# DE-020224_02.net
KiCad netlist of a schematic drawn in Altium Designer
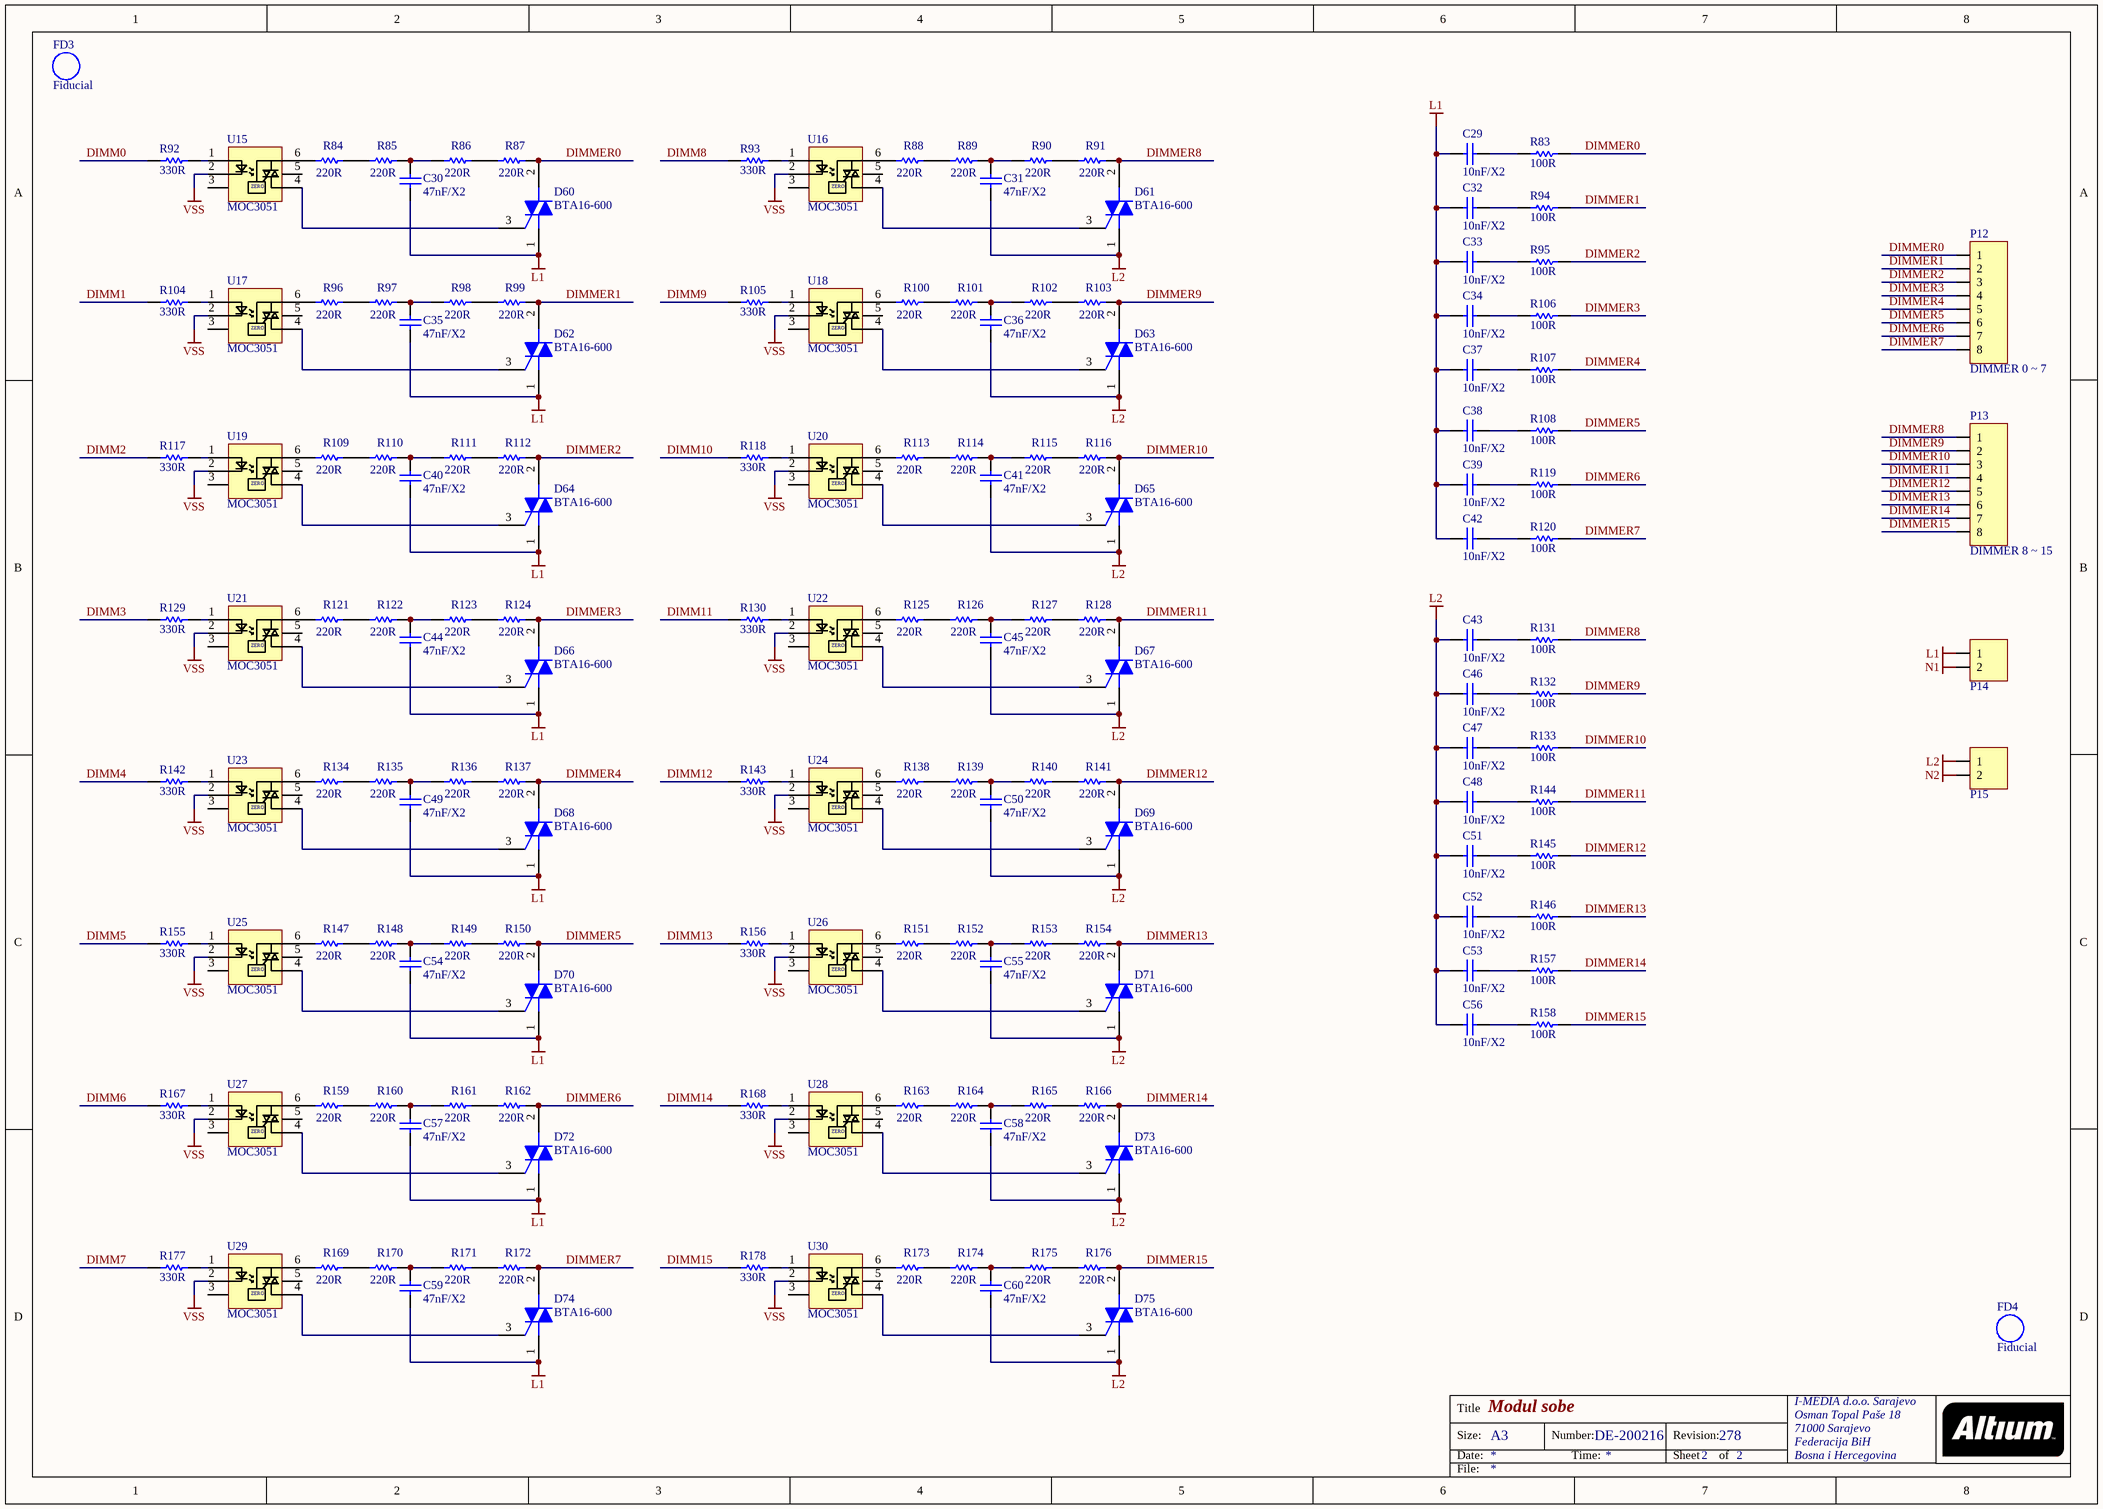
[diagram p0: DE-020224_02.SchDoc]

(export (version "E")
  (design (tool "Eeschema 10.0.6"))
  (components
    (comp (ref "C29")
      (value "10nF/X2")
      (footprint "VP52-2.5")
      (description "Dipped Radial Multilayer Ceramic Capacitor COG (NPO): 10nF")
      (fields (field (name "PUBLISHER") "Altium Limited"))
      (libsource (lib "Vishay Vitramon Ceramic Dipped Capacitor") (part "VP52BA103"))
    )
    (comp (ref "C30")
      (value "47nF/X2")
      (footprint "VP52-2.5")
      (description "Dipped Radial Multilayer Ceramic Capacitor COG (NPO): 10nF")
      (fields (field (name "PUBLISHER") "Altium Limited"))
      (libsource (lib "Vishay Vitramon Ceramic Dipped Capacitor") (part "VP52BA103"))
    )
    (comp (ref "C31")
      (value "47nF/X2")
      (footprint "VP52-2.5")
      (description "Dipped Radial Multilayer Ceramic Capacitor COG (NPO): 10nF")
      (fields (field (name "PUBLISHER") "Altium Limited"))
      (libsource (lib "Vishay Vitramon Ceramic Dipped Capacitor") (part "VP52BA103"))
    )
    (comp (ref "C32")
      (value "10nF/X2")
      (footprint "VP52-2.5")
      (description "Dipped Radial Multilayer Ceramic Capacitor COG (NPO): 10nF")
      (fields (field (name "PUBLISHER") "Altium Limited"))
      (libsource (lib "Vishay Vitramon Ceramic Dipped Capacitor") (part "VP52BA103"))
    )
    (comp (ref "C33")
      (value "10nF/X2")
      (footprint "VP52-2.5")
      (description "Dipped Radial Multilayer Ceramic Capacitor COG (NPO): 10nF")
      (fields (field (name "PUBLISHER") "Altium Limited"))
      (libsource (lib "Vishay Vitramon Ceramic Dipped Capacitor") (part "VP52BA103"))
    )
    (comp (ref "C34")
      (value "10nF/X2")
      (footprint "VP52-2.5")
      (description "Dipped Radial Multilayer Ceramic Capacitor COG (NPO): 10nF")
      (fields (field (name "PUBLISHER") "Altium Limited"))
      (libsource (lib "Vishay Vitramon Ceramic Dipped Capacitor") (part "VP52BA103"))
    )
    (comp (ref "C35")
      (value "47nF/X2")
      (footprint "VP52-2.5")
      (description "Dipped Radial Multilayer Ceramic Capacitor COG (NPO): 10nF")
      (fields (field (name "PUBLISHER") "Altium Limited"))
      (libsource (lib "Vishay Vitramon Ceramic Dipped Capacitor") (part "VP52BA103"))
    )
    (comp (ref "C36")
      (value "47nF/X2")
      (footprint "VP52-2.5")
      (description "Dipped Radial Multilayer Ceramic Capacitor COG (NPO): 10nF")
      (fields (field (name "PUBLISHER") "Altium Limited"))
      (libsource (lib "Vishay Vitramon Ceramic Dipped Capacitor") (part "VP52BA103"))
    )
    (comp (ref "C37")
      (value "10nF/X2")
      (footprint "VP52-2.5")
      (description "Dipped Radial Multilayer Ceramic Capacitor COG (NPO): 10nF")
      (fields (field (name "PUBLISHER") "Altium Limited"))
      (libsource (lib "Vishay Vitramon Ceramic Dipped Capacitor") (part "VP52BA103"))
    )
    (comp (ref "C38")
      (value "10nF/X2")
      (footprint "VP52-2.5")
      (description "Dipped Radial Multilayer Ceramic Capacitor COG (NPO): 10nF")
      (fields (field (name "PUBLISHER") "Altium Limited"))
      (libsource (lib "Vishay Vitramon Ceramic Dipped Capacitor") (part "VP52BA103"))
    )
    (comp (ref "C39")
      (value "10nF/X2")
      (footprint "VP52-2.5")
      (description "Dipped Radial Multilayer Ceramic Capacitor COG (NPO): 10nF")
      (fields (field (name "PUBLISHER") "Altium Limited"))
      (libsource (lib "Vishay Vitramon Ceramic Dipped Capacitor") (part "VP52BA103"))
    )
    (comp (ref "C40")
      (value "47nF/X2")
      (footprint "VP52-2.5")
      (description "Dipped Radial Multilayer Ceramic Capacitor COG (NPO): 10nF")
      (fields (field (name "PUBLISHER") "Altium Limited"))
      (libsource (lib "Vishay Vitramon Ceramic Dipped Capacitor") (part "VP52BA103"))
    )
    (comp (ref "C41")
      (value "47nF/X2")
      (footprint "VP52-2.5")
      (description "Dipped Radial Multilayer Ceramic Capacitor COG (NPO): 10nF")
      (fields (field (name "PUBLISHER") "Altium Limited"))
      (libsource (lib "Vishay Vitramon Ceramic Dipped Capacitor") (part "VP52BA103"))
    )
    (comp (ref "C42")
      (value "10nF/X2")
      (footprint "VP52-2.5")
      (description "Dipped Radial Multilayer Ceramic Capacitor COG (NPO): 10nF")
      (fields (field (name "PUBLISHER") "Altium Limited"))
      (libsource (lib "Vishay Vitramon Ceramic Dipped Capacitor") (part "VP52BA103"))
    )
    (comp (ref "C43")
      (value "10nF/X2")
      (footprint "VP52-2.5")
      (description "Dipped Radial Multilayer Ceramic Capacitor COG (NPO): 10nF")
      (fields (field (name "PUBLISHER") "Altium Limited"))
      (libsource (lib "Vishay Vitramon Ceramic Dipped Capacitor") (part "VP52BA103"))
    )
    (comp (ref "C44")
      (value "47nF/X2")
      (footprint "VP52-2.5")
      (description "Dipped Radial Multilayer Ceramic Capacitor COG (NPO): 10nF")
      (fields (field (name "PUBLISHER") "Altium Limited"))
      (libsource (lib "Vishay Vitramon Ceramic Dipped Capacitor") (part "VP52BA103"))
    )
    (comp (ref "C45")
      (value "47nF/X2")
      (footprint "VP52-2.5")
      (description "Dipped Radial Multilayer Ceramic Capacitor COG (NPO): 10nF")
      (fields (field (name "PUBLISHER") "Altium Limited"))
      (libsource (lib "Vishay Vitramon Ceramic Dipped Capacitor") (part "VP52BA103"))
    )
    (comp (ref "C46")
      (value "10nF/X2")
      (footprint "VP52-2.5")
      (description "Dipped Radial Multilayer Ceramic Capacitor COG (NPO): 10nF")
      (fields (field (name "PUBLISHER") "Altium Limited"))
      (libsource (lib "Vishay Vitramon Ceramic Dipped Capacitor") (part "VP52BA103"))
    )
    (comp (ref "C47")
      (value "10nF/X2")
      (footprint "VP52-2.5")
      (description "Dipped Radial Multilayer Ceramic Capacitor COG (NPO): 10nF")
      (fields (field (name "PUBLISHER") "Altium Limited"))
      (libsource (lib "Vishay Vitramon Ceramic Dipped Capacitor") (part "VP52BA103"))
    )
    (comp (ref "C48")
      (value "10nF/X2")
      (footprint "VP52-2.5")
      (description "Dipped Radial Multilayer Ceramic Capacitor COG (NPO): 10nF")
      (fields (field (name "PUBLISHER") "Altium Limited"))
      (libsource (lib "Vishay Vitramon Ceramic Dipped Capacitor") (part "VP52BA103"))
    )
    (comp (ref "C49")
      (value "47nF/X2")
      (footprint "VP52-2.5")
      (description "Dipped Radial Multilayer Ceramic Capacitor COG (NPO): 10nF")
      (fields (field (name "PUBLISHER") "Altium Limited"))
      (libsource (lib "Vishay Vitramon Ceramic Dipped Capacitor") (part "VP52BA103"))
    )
    (comp (ref "C50")
      (value "47nF/X2")
      (footprint "VP52-2.5")
      (description "Dipped Radial Multilayer Ceramic Capacitor COG (NPO): 10nF")
      (fields (field (name "PUBLISHER") "Altium Limited"))
      (libsource (lib "Vishay Vitramon Ceramic Dipped Capacitor") (part "VP52BA103"))
    )
    (comp (ref "C51")
      (value "10nF/X2")
      (footprint "VP52-2.5")
      (description "Dipped Radial Multilayer Ceramic Capacitor COG (NPO): 10nF")
      (fields (field (name "PUBLISHER") "Altium Limited"))
      (libsource (lib "Vishay Vitramon Ceramic Dipped Capacitor") (part "VP52BA103"))
    )
    (comp (ref "C52")
      (value "10nF/X2")
      (footprint "VP52-2.5")
      (description "Dipped Radial Multilayer Ceramic Capacitor COG (NPO): 10nF")
      (fields (field (name "PUBLISHER") "Altium Limited"))
      (libsource (lib "Vishay Vitramon Ceramic Dipped Capacitor") (part "VP52BA103"))
    )
    (comp (ref "C53")
      (value "10nF/X2")
      (footprint "VP52-2.5")
      (description "Dipped Radial Multilayer Ceramic Capacitor COG (NPO): 10nF")
      (fields (field (name "PUBLISHER") "Altium Limited"))
      (libsource (lib "Vishay Vitramon Ceramic Dipped Capacitor") (part "VP52BA103"))
    )
    (comp (ref "C54")
      (value "47nF/X2")
      (footprint "VP52-2.5")
      (description "Dipped Radial Multilayer Ceramic Capacitor COG (NPO): 10nF")
      (fields (field (name "PUBLISHER") "Altium Limited"))
      (libsource (lib "Vishay Vitramon Ceramic Dipped Capacitor") (part "VP52BA103"))
    )
    (comp (ref "C55")
      (value "47nF/X2")
      (footprint "VP52-2.5")
      (description "Dipped Radial Multilayer Ceramic Capacitor COG (NPO): 10nF")
      (fields (field (name "PUBLISHER") "Altium Limited"))
      (libsource (lib "Vishay Vitramon Ceramic Dipped Capacitor") (part "VP52BA103"))
    )
    (comp (ref "C56")
      (value "10nF/X2")
      (footprint "VP52-2.5")
      (description "Dipped Radial Multilayer Ceramic Capacitor COG (NPO): 10nF")
      (fields (field (name "PUBLISHER") "Altium Limited"))
      (libsource (lib "Vishay Vitramon Ceramic Dipped Capacitor") (part "VP52BA103"))
    )
    (comp (ref "C57")
      (value "47nF/X2")
      (footprint "VP52-2.5")
      (description "Dipped Radial Multilayer Ceramic Capacitor COG (NPO): 10nF")
      (fields (field (name "PUBLISHER") "Altium Limited"))
      (libsource (lib "Vishay Vitramon Ceramic Dipped Capacitor") (part "VP52BA103"))
    )
    (comp (ref "C58")
      (value "47nF/X2")
      (footprint "VP52-2.5")
      (description "Dipped Radial Multilayer Ceramic Capacitor COG (NPO): 10nF")
      (fields (field (name "PUBLISHER") "Altium Limited"))
      (libsource (lib "Vishay Vitramon Ceramic Dipped Capacitor") (part "VP52BA103"))
    )
    (comp (ref "C59")
      (value "47nF/X2")
      (footprint "VP52-2.5")
      (description "Dipped Radial Multilayer Ceramic Capacitor COG (NPO): 10nF")
      (fields (field (name "PUBLISHER") "Altium Limited"))
      (libsource (lib "Vishay Vitramon Ceramic Dipped Capacitor") (part "VP52BA103"))
    )
    (comp (ref "C60")
      (value "47nF/X2")
      (footprint "VP52-2.5")
      (description "Dipped Radial Multilayer Ceramic Capacitor COG (NPO): 10nF")
      (fields (field (name "PUBLISHER") "Altium Limited"))
      (libsource (lib "Vishay Vitramon Ceramic Dipped Capacitor") (part "VP52BA103"))
    )
    (comp (ref "D60")
      (value "BTA16-600")
      (footprint "ONSC-TO-220-3-221A-07")
      (description "Triacs, Silicon Bidirectional Thyristor, 3-Pin TO-220, Pb-Free, Tube")
      (fields (field (name "MANUFACTURER") "On Semiconductor") (field (name "PARTNUMBER") "BTA08-600BW3G"))
      (libsource (lib "DE-020224") (part "BTA08-600BW3G"))
    )
    (comp (ref "D61")
      (value "BTA16-600")
      (footprint "ONSC-TO-220-3-221A-07")
      (description "Triacs, Silicon Bidirectional Thyristor, 3-Pin TO-220, Pb-Free, Tube")
      (fields (field (name "MANUFACTURER") "On Semiconductor") (field (name "PARTNUMBER") "BTA08-600BW3G"))
      (libsource (lib "DE-020224") (part "BTA08-600BW3G"))
    )
    (comp (ref "D62")
      (value "BTA16-600")
      (footprint "ONSC-TO-220-3-221A-07")
      (description "Triacs, Silicon Bidirectional Thyristor, 3-Pin TO-220, Pb-Free, Tube")
      (fields (field (name "MANUFACTURER") "On Semiconductor") (field (name "PARTNUMBER") "BTA08-600BW3G"))
      (libsource (lib "DE-020224") (part "BTA08-600BW3G"))
    )
    (comp (ref "D63")
      (value "BTA16-600")
      (footprint "ONSC-TO-220-3-221A-07")
      (description "Triacs, Silicon Bidirectional Thyristor, 3-Pin TO-220, Pb-Free, Tube")
      (fields (field (name "MANUFACTURER") "On Semiconductor") (field (name "PARTNUMBER") "BTA08-600BW3G"))
      (libsource (lib "DE-020224") (part "BTA08-600BW3G"))
    )
    (comp (ref "D64")
      (value "BTA16-600")
      (footprint "ONSC-TO-220-3-221A-07")
      (description "Triacs, Silicon Bidirectional Thyristor, 3-Pin TO-220, Pb-Free, Tube")
      (fields (field (name "MANUFACTURER") "On Semiconductor") (field (name "PARTNUMBER") "BTA08-600BW3G"))
      (libsource (lib "DE-020224") (part "BTA08-600BW3G"))
    )
    (comp (ref "D65")
      (value "BTA16-600")
      (footprint "ONSC-TO-220-3-221A-07")
      (description "Triacs, Silicon Bidirectional Thyristor, 3-Pin TO-220, Pb-Free, Tube")
      (fields (field (name "MANUFACTURER") "On Semiconductor") (field (name "PARTNUMBER") "BTA08-600BW3G"))
      (libsource (lib "DE-020224") (part "BTA08-600BW3G"))
    )
    (comp (ref "D66")
      (value "BTA16-600")
      (footprint "ONSC-TO-220-3-221A-07")
      (description "Triacs, Silicon Bidirectional Thyristor, 3-Pin TO-220, Pb-Free, Tube")
      (fields (field (name "MANUFACTURER") "On Semiconductor") (field (name "PARTNUMBER") "BTA08-600BW3G"))
      (libsource (lib "DE-020224") (part "BTA08-600BW3G"))
    )
    (comp (ref "D67")
      (value "BTA16-600")
      (footprint "ONSC-TO-220-3-221A-07")
      (description "Triacs, Silicon Bidirectional Thyristor, 3-Pin TO-220, Pb-Free, Tube")
      (fields (field (name "MANUFACTURER") "On Semiconductor") (field (name "PARTNUMBER") "BTA08-600BW3G"))
      (libsource (lib "DE-020224") (part "BTA08-600BW3G"))
    )
    (comp (ref "D68")
      (value "BTA16-600")
      (footprint "ONSC-TO-220-3-221A-07")
      (description "Triacs, Silicon Bidirectional Thyristor, 3-Pin TO-220, Pb-Free, Tube")
      (fields (field (name "MANUFACTURER") "On Semiconductor") (field (name "PARTNUMBER") "BTA08-600BW3G"))
      (libsource (lib "DE-020224") (part "BTA08-600BW3G"))
    )
    (comp (ref "D69")
      (value "BTA16-600")
      (footprint "ONSC-TO-220-3-221A-07")
      (description "Triacs, Silicon Bidirectional Thyristor, 3-Pin TO-220, Pb-Free, Tube")
      (fields (field (name "MANUFACTURER") "On Semiconductor") (field (name "PARTNUMBER") "BTA08-600BW3G"))
      (libsource (lib "DE-020224") (part "BTA08-600BW3G"))
    )
    (comp (ref "D70")
      (value "BTA16-600")
      (footprint "ONSC-TO-220-3-221A-07")
      (description "Triacs, Silicon Bidirectional Thyristor, 3-Pin TO-220, Pb-Free, Tube")
      (fields (field (name "MANUFACTURER") "On Semiconductor") (field (name "PARTNUMBER") "BTA08-600BW3G"))
      (libsource (lib "DE-020224") (part "BTA08-600BW3G"))
    )
    (comp (ref "D71")
      (value "BTA16-600")
      (footprint "ONSC-TO-220-3-221A-07")
      (description "Triacs, Silicon Bidirectional Thyristor, 3-Pin TO-220, Pb-Free, Tube")
      (fields (field (name "MANUFACTURER") "On Semiconductor") (field (name "PARTNUMBER") "BTA08-600BW3G"))
      (libsource (lib "DE-020224") (part "BTA08-600BW3G"))
    )
    (comp (ref "D72")
      (value "BTA16-600")
      (footprint "ONSC-TO-220-3-221A-07")
      (description "Triacs, Silicon Bidirectional Thyristor, 3-Pin TO-220, Pb-Free, Tube")
      (fields (field (name "MANUFACTURER") "On Semiconductor") (field (name "PARTNUMBER") "BTA08-600BW3G"))
      (libsource (lib "DE-020224") (part "BTA08-600BW3G"))
    )
    (comp (ref "D73")
      (value "BTA16-600")
      (footprint "ONSC-TO-220-3-221A-07")
      (description "Triacs, Silicon Bidirectional Thyristor, 3-Pin TO-220, Pb-Free, Tube")
      (fields (field (name "MANUFACTURER") "On Semiconductor") (field (name "PARTNUMBER") "BTA08-600BW3G"))
      (libsource (lib "DE-020224") (part "BTA08-600BW3G"))
    )
    (comp (ref "D74")
      (value "BTA16-600")
      (footprint "ONSC-TO-220-3-221A-07")
      (description "Triacs, Silicon Bidirectional Thyristor, 3-Pin TO-220, Pb-Free, Tube")
      (fields (field (name "MANUFACTURER") "On Semiconductor") (field (name "PARTNUMBER") "BTA08-600BW3G"))
      (libsource (lib "DE-020224") (part "BTA08-600BW3G"))
    )
    (comp (ref "D75")
      (value "BTA16-600")
      (footprint "ONSC-TO-220-3-221A-07")
      (description "Triacs, Silicon Bidirectional Thyristor, 3-Pin TO-220, Pb-Free, Tube")
      (fields (field (name "MANUFACTURER") "On Semiconductor") (field (name "PARTNUMBER") "BTA08-600BW3G"))
      (libsource (lib "DE-020224") (part "BTA08-600BW3G"))
    )
    (comp (ref "FD3")
      (value "Fiducial")
      (footprint "Fiducial")
      (description "Fiduchial mark")
      (libsource (lib "DE-200216_02_1") (part "Fiduchial"))
    )
    (comp (ref "FD4")
      (value "Fiducial")
      (footprint "Fiducial")
      (description "Fiduchial mark")
      (libsource (lib "DE-200216_02_1") (part "Fiduchial"))
    )
    (comp (ref "P12")
      (value "DIMMER 0 ~ 7")
      (footprint "TERMINAL BLOK 8")
      (description "8 pin terminal cable connector")
      (libsource (lib "DE-020224") (part "TERMINAL BLOK 8 MANJI"))
    )
    (comp (ref "P13")
      (value "DIMMER 8 ~ 15")
      (footprint "TERMINAL BLOK 8")
      (description "8 pin terminal cable connector")
      (libsource (lib "DE-020224") (part "TERMINAL BLOK 8 MANJI"))
    )
    (comp (ref "P14")
      (value "TERMINAL BLOK 2")
      (footprint "TERMINAL BLOK 2")
      (description "2 pinski terminal blok")
      (libsource (lib "DE-020224") (part "TERMINAL BLOK 2"))
    )
    (comp (ref "P15")
      (value "TERMINAL BLOK 2")
      (footprint "TERMINAL BLOK 2")
      (description "2 pinski terminal blok")
      (libsource (lib "DE-020224") (part "TERMINAL BLOK 2"))
    )
    (comp (ref "R83")
      (value "100R")
      (footprint "R6.35x2.3")
      (description "Metal Oxide Film Resistor, 0.1 Ohm to 47k Ohm Range, 2% and 5% Tolerance, 0.5 W")
      (fields (field (name "PUBLISHER") "Altium Limited"))
      (libsource (lib "DE-020224") (part "ERG12"))
    )
    (comp (ref "R84")
      (value "220R")
      (footprint "ERA-0805")
      (fields (field (name "PUBLISHER") "Altium Limited"))
      (libsource (lib "DE-020224") (part "ERA6Y"))
    )
    (comp (ref "R85")
      (value "220R")
      (footprint "ERA-0805")
      (fields (field (name "PUBLISHER") "Altium Limited"))
      (libsource (lib "DE-020224") (part "ERA6Y"))
    )
    (comp (ref "R86")
      (value "220R")
      (footprint "ERA-0805")
      (fields (field (name "PUBLISHER") "Altium Limited"))
      (libsource (lib "DE-020224") (part "ERA6Y"))
    )
    (comp (ref "R87")
      (value "220R")
      (footprint "ERA-0805")
      (fields (field (name "PUBLISHER") "Altium Limited"))
      (libsource (lib "DE-020224") (part "ERA6Y"))
    )
    (comp (ref "R88")
      (value "220R")
      (footprint "ERA-0805")
      (fields (field (name "PUBLISHER") "Altium Limited"))
      (libsource (lib "DE-020224") (part "ERA6Y"))
    )
    (comp (ref "R89")
      (value "220R")
      (footprint "ERA-0805")
      (fields (field (name "PUBLISHER") "Altium Limited"))
      (libsource (lib "DE-020224") (part "ERA6Y"))
    )
    (comp (ref "R90")
      (value "220R")
      (footprint "ERA-0805")
      (fields (field (name "PUBLISHER") "Altium Limited"))
      (libsource (lib "DE-020224") (part "ERA6Y"))
    )
    (comp (ref "R91")
      (value "220R")
      (footprint "ERA-0805")
      (fields (field (name "PUBLISHER") "Altium Limited"))
      (libsource (lib "DE-020224") (part "ERA6Y"))
    )
    (comp (ref "R92")
      (value "330R")
      (footprint "ERA-0603")
      (fields (field (name "PUBLISHER") "Altium Limited"))
      (libsource (lib "DE-020224") (part "ERA3Y"))
    )
    (comp (ref "R93")
      (value "330R")
      (footprint "ERA-0603")
      (fields (field (name "PUBLISHER") "Altium Limited"))
      (libsource (lib "DE-020224") (part "ERA3Y"))
    )
    (comp (ref "R94")
      (value "100R")
      (footprint "R6.35x2.3")
      (description "Metal Oxide Film Resistor, 0.1 Ohm to 47k Ohm Range, 2% and 5% Tolerance, 0.5 W")
      (fields (field (name "PUBLISHER") "Altium Limited"))
      (libsource (lib "DE-020224") (part "ERG12"))
    )
    (comp (ref "R95")
      (value "100R")
      (footprint "R6.35x2.3")
      (description "Metal Oxide Film Resistor, 0.1 Ohm to 47k Ohm Range, 2% and 5% Tolerance, 0.5 W")
      (fields (field (name "PUBLISHER") "Altium Limited"))
      (libsource (lib "DE-020224") (part "ERG12"))
    )
    (comp (ref "R96")
      (value "220R")
      (footprint "ERA-0805")
      (fields (field (name "PUBLISHER") "Altium Limited"))
      (libsource (lib "DE-020224") (part "ERA6Y"))
    )
    (comp (ref "R97")
      (value "220R")
      (footprint "ERA-0805")
      (fields (field (name "PUBLISHER") "Altium Limited"))
      (libsource (lib "DE-020224") (part "ERA6Y"))
    )
    (comp (ref "R98")
      (value "220R")
      (footprint "ERA-0805")
      (fields (field (name "PUBLISHER") "Altium Limited"))
      (libsource (lib "DE-020224") (part "ERA6Y"))
    )
    (comp (ref "R99")
      (value "220R")
      (footprint "ERA-0805")
      (fields (field (name "PUBLISHER") "Altium Limited"))
      (libsource (lib "DE-020224") (part "ERA6Y"))
    )
    (comp (ref "R100")
      (value "220R")
      (footprint "ERA-0805")
      (fields (field (name "PUBLISHER") "Altium Limited"))
      (libsource (lib "DE-020224") (part "ERA6Y"))
    )
    (comp (ref "R101")
      (value "220R")
      (footprint "ERA-0805")
      (fields (field (name "PUBLISHER") "Altium Limited"))
      (libsource (lib "DE-020224") (part "ERA6Y"))
    )
    (comp (ref "R102")
      (value "220R")
      (footprint "ERA-0805")
      (fields (field (name "PUBLISHER") "Altium Limited"))
      (libsource (lib "DE-020224") (part "ERA6Y"))
    )
    (comp (ref "R103")
      (value "220R")
      (footprint "ERA-0805")
      (fields (field (name "PUBLISHER") "Altium Limited"))
      (libsource (lib "DE-020224") (part "ERA6Y"))
    )
    (comp (ref "R104")
      (value "330R")
      (footprint "ERA-0603")
      (fields (field (name "PUBLISHER") "Altium Limited"))
      (libsource (lib "DE-020224") (part "ERA3Y"))
    )
    (comp (ref "R105")
      (value "330R")
      (footprint "ERA-0603")
      (fields (field (name "PUBLISHER") "Altium Limited"))
      (libsource (lib "DE-020224") (part "ERA3Y"))
    )
    (comp (ref "R106")
      (value "100R")
      (footprint "R6.35x2.3")
      (description "Metal Oxide Film Resistor, 0.1 Ohm to 47k Ohm Range, 2% and 5% Tolerance, 0.5 W")
      (fields (field (name "PUBLISHER") "Altium Limited"))
      (libsource (lib "DE-020224") (part "ERG12"))
    )
    (comp (ref "R107")
      (value "100R")
      (footprint "R6.35x2.3")
      (description "Metal Oxide Film Resistor, 0.1 Ohm to 47k Ohm Range, 2% and 5% Tolerance, 0.5 W")
      (fields (field (name "PUBLISHER") "Altium Limited"))
      (libsource (lib "DE-020224") (part "ERG12"))
    )
    (comp (ref "R108")
      (value "100R")
      (footprint "R6.35x2.3")
      (description "Metal Oxide Film Resistor, 0.1 Ohm to 47k Ohm Range, 2% and 5% Tolerance, 0.5 W")
      (fields (field (name "PUBLISHER") "Altium Limited"))
      (libsource (lib "DE-020224") (part "ERG12"))
    )
    (comp (ref "R109")
      (value "220R")
      (footprint "ERA-0805")
      (fields (field (name "PUBLISHER") "Altium Limited"))
      (libsource (lib "DE-020224") (part "ERA6Y"))
    )
    (comp (ref "R110")
      (value "220R")
      (footprint "ERA-0805")
      (fields (field (name "PUBLISHER") "Altium Limited"))
      (libsource (lib "DE-020224") (part "ERA6Y"))
    )
    (comp (ref "R111")
      (value "220R")
      (footprint "ERA-0805")
      (fields (field (name "PUBLISHER") "Altium Limited"))
      (libsource (lib "DE-020224") (part "ERA6Y"))
    )
    (comp (ref "R112")
      (value "220R")
      (footprint "ERA-0805")
      (fields (field (name "PUBLISHER") "Altium Limited"))
      (libsource (lib "DE-020224") (part "ERA6Y"))
    )
    (comp (ref "R113")
      (value "220R")
      (footprint "ERA-0805")
      (fields (field (name "PUBLISHER") "Altium Limited"))
      (libsource (lib "DE-020224") (part "ERA6Y"))
    )
    (comp (ref "R114")
      (value "220R")
      (footprint "ERA-0805")
      (fields (field (name "PUBLISHER") "Altium Limited"))
      (libsource (lib "DE-020224") (part "ERA6Y"))
    )
    (comp (ref "R115")
      (value "220R")
      (footprint "ERA-0805")
      (fields (field (name "PUBLISHER") "Altium Limited"))
      (libsource (lib "DE-020224") (part "ERA6Y"))
    )
    (comp (ref "R116")
      (value "220R")
      (footprint "ERA-0805")
      (fields (field (name "PUBLISHER") "Altium Limited"))
      (libsource (lib "DE-020224") (part "ERA6Y"))
    )
    (comp (ref "R117")
      (value "330R")
      (footprint "ERA-0603")
      (fields (field (name "PUBLISHER") "Altium Limited"))
      (libsource (lib "DE-020224") (part "ERA3Y"))
    )
    (comp (ref "R118")
      (value "330R")
      (footprint "ERA-0603")
      (fields (field (name "PUBLISHER") "Altium Limited"))
      (libsource (lib "DE-020224") (part "ERA3Y"))
    )
    (comp (ref "R119")
      (value "100R")
      (footprint "R6.35x2.3")
      (description "Metal Oxide Film Resistor, 0.1 Ohm to 47k Ohm Range, 2% and 5% Tolerance, 0.5 W")
      (fields (field (name "PUBLISHER") "Altium Limited"))
      (libsource (lib "DE-020224") (part "ERG12"))
    )
    (comp (ref "R120")
      (value "100R")
      (footprint "R6.35x2.3")
      (description "Metal Oxide Film Resistor, 0.1 Ohm to 47k Ohm Range, 2% and 5% Tolerance, 0.5 W")
      (fields (field (name "PUBLISHER") "Altium Limited"))
      (libsource (lib "DE-020224") (part "ERG12"))
    )
    (comp (ref "R121")
      (value "220R")
      (footprint "ERA-0805")
      (fields (field (name "PUBLISHER") "Altium Limited"))
      (libsource (lib "DE-020224") (part "ERA6Y"))
    )
    (comp (ref "R122")
      (value "220R")
      (footprint "ERA-0805")
      (fields (field (name "PUBLISHER") "Altium Limited"))
      (libsource (lib "DE-020224") (part "ERA6Y"))
    )
    (comp (ref "R123")
      (value "220R")
      (footprint "ERA-0805")
      (fields (field (name "PUBLISHER") "Altium Limited"))
      (libsource (lib "DE-020224") (part "ERA6Y"))
    )
    (comp (ref "R124")
      (value "220R")
      (footprint "ERA-0805")
      (fields (field (name "PUBLISHER") "Altium Limited"))
      (libsource (lib "DE-020224") (part "ERA6Y"))
    )
    (comp (ref "R125")
      (value "220R")
      (footprint "ERA-0805")
      (fields (field (name "PUBLISHER") "Altium Limited"))
      (libsource (lib "DE-020224") (part "ERA6Y"))
    )
    (comp (ref "R126")
      (value "220R")
      (footprint "ERA-0805")
      (fields (field (name "PUBLISHER") "Altium Limited"))
      (libsource (lib "DE-020224") (part "ERA6Y"))
    )
    (comp (ref "R127")
      (value "220R")
      (footprint "ERA-0805")
      (fields (field (name "PUBLISHER") "Altium Limited"))
      (libsource (lib "DE-020224") (part "ERA6Y"))
    )
    (comp (ref "R128")
      (value "220R")
      (footprint "ERA-0805")
      (fields (field (name "PUBLISHER") "Altium Limited"))
      (libsource (lib "DE-020224") (part "ERA6Y"))
    )
    (comp (ref "R129")
      (value "330R")
      (footprint "ERA-0603")
      (fields (field (name "PUBLISHER") "Altium Limited"))
      (libsource (lib "DE-020224") (part "ERA3Y"))
    )
    (comp (ref "R130")
      (value "330R")
      (footprint "ERA-0603")
      (fields (field (name "PUBLISHER") "Altium Limited"))
      (libsource (lib "DE-020224") (part "ERA3Y"))
    )
    (comp (ref "R131")
      (value "100R")
      (footprint "R6.35x2.3")
      (description "Metal Oxide Film Resistor, 0.1 Ohm to 47k Ohm Range, 2% and 5% Tolerance, 0.5 W")
      (fields (field (name "PUBLISHER") "Altium Limited"))
      (libsource (lib "DE-020224") (part "ERG12"))
    )
    (comp (ref "R132")
      (value "100R")
      (footprint "R6.35x2.3")
      (description "Metal Oxide Film Resistor, 0.1 Ohm to 47k Ohm Range, 2% and 5% Tolerance, 0.5 W")
      (fields (field (name "PUBLISHER") "Altium Limited"))
      (libsource (lib "DE-020224") (part "ERG12"))
    )
    (comp (ref "R133")
      (value "100R")
      (footprint "R6.35x2.3")
      (description "Metal Oxide Film Resistor, 0.1 Ohm to 47k Ohm Range, 2% and 5% Tolerance, 0.5 W")
      (fields (field (name "PUBLISHER") "Altium Limited"))
      (libsource (lib "DE-020224") (part "ERG12"))
    )
    (comp (ref "R134")
      (value "220R")
      (footprint "ERA-0805")
      (fields (field (name "PUBLISHER") "Altium Limited"))
      (libsource (lib "DE-020224") (part "ERA6Y"))
    )
    (comp (ref "R135")
      (value "220R")
      (footprint "ERA-0805")
      (fields (field (name "PUBLISHER") "Altium Limited"))
      (libsource (lib "DE-020224") (part "ERA6Y"))
    )
    (comp (ref "R136")
      (value "220R")
      (footprint "ERA-0805")
      (fields (field (name "PUBLISHER") "Altium Limited"))
      (libsource (lib "DE-020224") (part "ERA6Y"))
    )
    (comp (ref "R137")
      (value "220R")
      (footprint "ERA-0805")
      (fields (field (name "PUBLISHER") "Altium Limited"))
      (libsource (lib "DE-020224") (part "ERA6Y"))
    )
    (comp (ref "R138")
      (value "220R")
      (footprint "ERA-0805")
      (fields (field (name "PUBLISHER") "Altium Limited"))
      (libsource (lib "DE-020224") (part "ERA6Y"))
    )
    (comp (ref "R139")
      (value "220R")
      (footprint "ERA-0805")
      (fields (field (name "PUBLISHER") "Altium Limited"))
      (libsource (lib "DE-020224") (part "ERA6Y"))
    )
    (comp (ref "R140")
      (value "220R")
      (footprint "ERA-0805")
      (fields (field (name "PUBLISHER") "Altium Limited"))
      (libsource (lib "DE-020224") (part "ERA6Y"))
    )
    (comp (ref "R141")
      (value "220R")
      (footprint "ERA-0805")
      (fields (field (name "PUBLISHER") "Altium Limited"))
      (libsource (lib "DE-020224") (part "ERA6Y"))
    )
    (comp (ref "R142")
      (value "330R")
      (footprint "ERA-0603")
      (fields (field (name "PUBLISHER") "Altium Limited"))
      (libsource (lib "DE-020224") (part "ERA3Y"))
    )
    (comp (ref "R143")
      (value "330R")
      (footprint "ERA-0603")
      (fields (field (name "PUBLISHER") "Altium Limited"))
      (libsource (lib "DE-020224") (part "ERA3Y"))
    )
    (comp (ref "R144")
      (value "100R")
      (footprint "R6.35x2.3")
      (description "Metal Oxide Film Resistor, 0.1 Ohm to 47k Ohm Range, 2% and 5% Tolerance, 0.5 W")
      (fields (field (name "PUBLISHER") "Altium Limited"))
      (libsource (lib "DE-020224") (part "ERG12"))
    )
    (comp (ref "R145")
      (value "100R")
      (footprint "R6.35x2.3")
      (description "Metal Oxide Film Resistor, 0.1 Ohm to 47k Ohm Range, 2% and 5% Tolerance, 0.5 W")
      (fields (field (name "PUBLISHER") "Altium Limited"))
      (libsource (lib "DE-020224") (part "ERG12"))
    )
    (comp (ref "R146")
      (value "100R")
      (footprint "R6.35x2.3")
      (description "Metal Oxide Film Resistor, 0.1 Ohm to 47k Ohm Range, 2% and 5% Tolerance, 0.5 W")
      (fields (field (name "PUBLISHER") "Altium Limited"))
      (libsource (lib "DE-020224") (part "ERG12"))
    )
    (comp (ref "R147")
      (value "220R")
      (footprint "ERA-0805")
      (fields (field (name "PUBLISHER") "Altium Limited"))
      (libsource (lib "DE-020224") (part "ERA6Y"))
    )
    (comp (ref "R148")
      (value "220R")
      (footprint "ERA-0805")
      (fields (field (name "PUBLISHER") "Altium Limited"))
      (libsource (lib "DE-020224") (part "ERA6Y"))
    )
    (comp (ref "R149")
      (value "220R")
      (footprint "ERA-0805")
      (fields (field (name "PUBLISHER") "Altium Limited"))
      (libsource (lib "DE-020224") (part "ERA6Y"))
    )
    (comp (ref "R150")
      (value "220R")
      (footprint "ERA-0805")
      (fields (field (name "PUBLISHER") "Altium Limited"))
      (libsource (lib "DE-020224") (part "ERA6Y"))
    )
    (comp (ref "R151")
      (value "220R")
      (footprint "ERA-0805")
      (fields (field (name "PUBLISHER") "Altium Limited"))
      (libsource (lib "DE-020224") (part "ERA6Y"))
    )
    (comp (ref "R152")
      (value "220R")
      (footprint "ERA-0805")
      (fields (field (name "PUBLISHER") "Altium Limited"))
      (libsource (lib "DE-020224") (part "ERA6Y"))
    )
    (comp (ref "R153")
      (value "220R")
      (footprint "ERA-0805")
      (fields (field (name "PUBLISHER") "Altium Limited"))
      (libsource (lib "DE-020224") (part "ERA6Y"))
    )
    (comp (ref "R154")
      (value "220R")
      (footprint "ERA-0805")
      (fields (field (name "PUBLISHER") "Altium Limited"))
      (libsource (lib "DE-020224") (part "ERA6Y"))
    )
    (comp (ref "R155")
      (value "330R")
      (footprint "ERA-0603")
      (fields (field (name "PUBLISHER") "Altium Limited"))
      (libsource (lib "DE-020224") (part "ERA3Y"))
    )
    (comp (ref "R156")
      (value "330R")
      (footprint "ERA-0603")
      (fields (field (name "PUBLISHER") "Altium Limited"))
      (libsource (lib "DE-020224") (part "ERA3Y"))
    )
    (comp (ref "R157")
      (value "100R")
      (footprint "R6.35x2.3")
      (description "Metal Oxide Film Resistor, 0.1 Ohm to 47k Ohm Range, 2% and 5% Tolerance, 0.5 W")
      (fields (field (name "PUBLISHER") "Altium Limited"))
      (libsource (lib "DE-020224") (part "ERG12"))
    )
    (comp (ref "R158")
      (value "100R")
      (footprint "R6.35x2.3")
      (description "Metal Oxide Film Resistor, 0.1 Ohm to 47k Ohm Range, 2% and 5% Tolerance, 0.5 W")
      (fields (field (name "PUBLISHER") "Altium Limited"))
      (libsource (lib "DE-020224") (part "ERG12"))
    )
    (comp (ref "R159")
      (value "220R")
      (footprint "ERA-0805")
      (fields (field (name "PUBLISHER") "Altium Limited"))
      (libsource (lib "DE-020224") (part "ERA6Y"))
    )
    (comp (ref "R160")
      (value "220R")
      (footprint "ERA-0805")
      (fields (field (name "PUBLISHER") "Altium Limited"))
      (libsource (lib "DE-020224") (part "ERA6Y"))
    )
    (comp (ref "R161")
      (value "220R")
      (footprint "ERA-0805")
      (fields (field (name "PUBLISHER") "Altium Limited"))
      (libsource (lib "DE-020224") (part "ERA6Y"))
    )
    (comp (ref "R162")
      (value "220R")
      (footprint "ERA-0805")
      (fields (field (name "PUBLISHER") "Altium Limited"))
      (libsource (lib "DE-020224") (part "ERA6Y"))
    )
    (comp (ref "R163")
      (value "220R")
      (footprint "ERA-0805")
      (fields (field (name "PUBLISHER") "Altium Limited"))
      (libsource (lib "DE-020224") (part "ERA6Y"))
    )
    (comp (ref "R164")
      (value "220R")
      (footprint "ERA-0805")
      (fields (field (name "PUBLISHER") "Altium Limited"))
      (libsource (lib "DE-020224") (part "ERA6Y"))
    )
    (comp (ref "R165")
      (value "220R")
      (footprint "ERA-0805")
      (fields (field (name "PUBLISHER") "Altium Limited"))
      (libsource (lib "DE-020224") (part "ERA6Y"))
    )
    (comp (ref "R166")
      (value "220R")
      (footprint "ERA-0805")
      (fields (field (name "PUBLISHER") "Altium Limited"))
      (libsource (lib "DE-020224") (part "ERA6Y"))
    )
    (comp (ref "R167")
      (value "330R")
      (footprint "ERA-0603")
      (fields (field (name "PUBLISHER") "Altium Limited"))
      (libsource (lib "DE-020224") (part "ERA3Y"))
    )
    (comp (ref "R168")
      (value "330R")
      (footprint "ERA-0603")
      (fields (field (name "PUBLISHER") "Altium Limited"))
      (libsource (lib "DE-020224") (part "ERA3Y"))
    )
    (comp (ref "R169")
      (value "220R")
      (footprint "ERA-0805")
      (fields (field (name "PUBLISHER") "Altium Limited"))
      (libsource (lib "DE-020224") (part "ERA6Y"))
    )
    (comp (ref "R170")
      (value "220R")
      (footprint "ERA-0805")
      (fields (field (name "PUBLISHER") "Altium Limited"))
      (libsource (lib "DE-020224") (part "ERA6Y"))
    )
    (comp (ref "R171")
      (value "220R")
      (footprint "ERA-0805")
      (fields (field (name "PUBLISHER") "Altium Limited"))
      (libsource (lib "DE-020224") (part "ERA6Y"))
    )
    (comp (ref "R172")
      (value "220R")
      (footprint "ERA-0805")
      (fields (field (name "PUBLISHER") "Altium Limited"))
      (libsource (lib "DE-020224") (part "ERA6Y"))
    )
    (comp (ref "R173")
      (value "220R")
      (footprint "ERA-0805")
      (fields (field (name "PUBLISHER") "Altium Limited"))
      (libsource (lib "DE-020224") (part "ERA6Y"))
    )
    (comp (ref "R174")
      (value "220R")
      (footprint "ERA-0805")
      (fields (field (name "PUBLISHER") "Altium Limited"))
      (libsource (lib "DE-020224") (part "ERA6Y"))
    )
    (comp (ref "R175")
      (value "220R")
      (footprint "ERA-0805")
      (fields (field (name "PUBLISHER") "Altium Limited"))
      (libsource (lib "DE-020224") (part "ERA6Y"))
    )
    (comp (ref "R176")
      (value "220R")
      (footprint "ERA-0805")
      (fields (field (name "PUBLISHER") "Altium Limited"))
      (libsource (lib "DE-020224") (part "ERA6Y"))
    )
    (comp (ref "R177")
      (value "330R")
      (footprint "ERA-0603")
      (fields (field (name "PUBLISHER") "Altium Limited"))
      (libsource (lib "DE-020224") (part "ERA3Y"))
    )
    (comp (ref "R178")
      (value "330R")
      (footprint "ERA-0603")
      (fields (field (name "PUBLISHER") "Altium Limited"))
      (libsource (lib "DE-020224") (part "ERA3Y"))
    )
    (comp (ref "U15")
      (value "MOC3051")
      (footprint "DIP6")
      (description "Zero-Cross Optoisolator Triac Driver")
      (libsource (lib "DE-020224") (part "MOC3081"))
    )
    (comp (ref "U16")
      (value "MOC3051")
      (footprint "DIP6")
      (description "Zero-Cross Optoisolator Triac Driver")
      (libsource (lib "DE-020224") (part "MOC3081"))
    )
    (comp (ref "U17")
      (value "MOC3051")
      (footprint "DIP6")
      (description "Zero-Cross Optoisolator Triac Driver")
      (libsource (lib "DE-020224") (part "MOC3081"))
    )
    (comp (ref "U18")
      (value "MOC3051")
      (footprint "DIP6")
      (description "Zero-Cross Optoisolator Triac Driver")
      (libsource (lib "DE-020224") (part "MOC3081"))
    )
    (comp (ref "U19")
      (value "MOC3051")
      (footprint "DIP6")
      (description "Zero-Cross Optoisolator Triac Driver")
      (libsource (lib "DE-020224") (part "MOC3081"))
    )
    (comp (ref "U20")
      (value "MOC3051")
      (footprint "DIP6")
      (description "Zero-Cross Optoisolator Triac Driver")
      (libsource (lib "DE-020224") (part "MOC3081"))
    )
    (comp (ref "U21")
      (value "MOC3051")
      (footprint "DIP6")
      (description "Zero-Cross Optoisolator Triac Driver")
      (libsource (lib "DE-020224") (part "MOC3081"))
    )
    (comp (ref "U22")
      (value "MOC3051")
      (footprint "DIP6")
      (description "Zero-Cross Optoisolator Triac Driver")
      (libsource (lib "DE-020224") (part "MOC3081"))
    )
    (comp (ref "U23")
      (value "MOC3051")
      (footprint "DIP6")
      (description "Zero-Cross Optoisolator Triac Driver")
      (libsource (lib "DE-020224") (part "MOC3081"))
    )
    (comp (ref "U24")
      (value "MOC3051")
      (footprint "DIP6")
      (description "Zero-Cross Optoisolator Triac Driver")
      (libsource (lib "DE-020224") (part "MOC3081"))
    )
    (comp (ref "U25")
      (value "MOC3051")
      (footprint "DIP6")
      (description "Zero-Cross Optoisolator Triac Driver")
      (libsource (lib "DE-020224") (part "MOC3081"))
    )
    (comp (ref "U26")
      (value "MOC3051")
      (footprint "DIP6")
      (description "Zero-Cross Optoisolator Triac Driver")
      (libsource (lib "DE-020224") (part "MOC3081"))
    )
    (comp (ref "U27")
      (value "MOC3051")
      (footprint "DIP6")
      (description "Zero-Cross Optoisolator Triac Driver")
      (libsource (lib "DE-020224") (part "MOC3081"))
    )
    (comp (ref "U28")
      (value "MOC3051")
      (footprint "DIP6")
      (description "Zero-Cross Optoisolator Triac Driver")
      (libsource (lib "DE-020224") (part "MOC3081"))
    )
    (comp (ref "U29")
      (value "MOC3051")
      (footprint "DIP6")
      (description "Zero-Cross Optoisolator Triac Driver")
      (libsource (lib "DE-020224") (part "MOC3081"))
    )
    (comp (ref "U30")
      (value "MOC3051")
      (footprint "DIP6")
      (description "Zero-Cross Optoisolator Triac Driver")
      (libsource (lib "DE-020224") (part "MOC3081"))
    )
  )
  (nets
    (net (code "1") (name "/DIMM0") (class "Default")
      (node (ref "R92") (pin "1") (pinfunction "1_1") (pintype "passive"))
    )
    (net (code "2") (name "/DIMM1") (class "Default")
      (node (ref "R104") (pin "1") (pinfunction "1_1") (pintype "passive"))
    )
    (net (code "3") (name "/DIMM2") (class "Default")
      (node (ref "R117") (pin "1") (pinfunction "1_1") (pintype "passive"))
    )
    (net (code "4") (name "/DIMM3") (class "Default")
      (node (ref "R129") (pin "1") (pinfunction "1_1") (pintype "passive"))
    )
    (net (code "5") (name "/DIMM4") (class "Default")
      (node (ref "R142") (pin "1") (pinfunction "1_1") (pintype "passive"))
    )
    (net (code "6") (name "/DIMM5") (class "Default")
      (node (ref "R155") (pin "1") (pinfunction "1_1") (pintype "passive"))
    )
    (net (code "7") (name "/DIMM6") (class "Default")
      (node (ref "R167") (pin "1") (pinfunction "1_1") (pintype "passive"))
    )
    (net (code "8") (name "/DIMM7") (class "Default")
      (node (ref "R177") (pin "1") (pinfunction "1_1") (pintype "passive"))
    )
    (net (code "9") (name "/DIMM8") (class "Default")
      (node (ref "R93") (pin "1") (pinfunction "1_1") (pintype "passive"))
    )
    (net (code "10") (name "/DIMM9") (class "Default")
      (node (ref "R105") (pin "1") (pinfunction "1_1") (pintype "passive"))
    )
    (net (code "11") (name "/DIMM10") (class "Default")
      (node (ref "R118") (pin "1") (pinfunction "1_1") (pintype "passive"))
    )
    (net (code "12") (name "/DIMM11") (class "Default")
      (node (ref "R130") (pin "1") (pinfunction "1_1") (pintype "passive"))
    )
    (net (code "13") (name "/DIMM12") (class "Default")
      (node (ref "R143") (pin "1") (pinfunction "1_1") (pintype "passive"))
    )
    (net (code "14") (name "/DIMM13") (class "Default")
      (node (ref "R156") (pin "1") (pinfunction "1_1") (pintype "passive"))
    )
    (net (code "15") (name "/DIMM14") (class "Default")
      (node (ref "R168") (pin "1") (pinfunction "1_1") (pintype "passive"))
    )
    (net (code "16") (name "/DIMM15") (class "Default")
      (node (ref "R178") (pin "1") (pinfunction "1_1") (pintype "passive"))
    )
    (net (code "17") (name "/DIMMER0") (class "Default")
      (node (ref "D60") (pin "2") (pinfunction "MT2_2") (pintype "passive"))
      (node (ref "P12") (pin "1") (pinfunction "1_1") (pintype "passive"))
      (node (ref "R83") (pin "1") (pinfunction "1_1") (pintype "passive"))
      (node (ref "R87") (pin "2") (pinfunction "2_2") (pintype "passive"))
    )
    (net (code "18") (name "/DIMMER1") (class "Default")
      (node (ref "D62") (pin "2") (pinfunction "MT2_2") (pintype "passive"))
      (node (ref "P12") (pin "2") (pinfunction "2_2") (pintype "passive"))
      (node (ref "R94") (pin "1") (pinfunction "1_1") (pintype "passive"))
      (node (ref "R99") (pin "2") (pinfunction "2_2") (pintype "passive"))
    )
    (net (code "19") (name "/DIMMER2") (class "Default")
      (node (ref "D64") (pin "2") (pinfunction "MT2_2") (pintype "passive"))
      (node (ref "P12") (pin "3") (pinfunction "3_3") (pintype "passive"))
      (node (ref "R112") (pin "2") (pinfunction "2_2") (pintype "passive"))
      (node (ref "R95") (pin "1") (pinfunction "1_1") (pintype "passive"))
    )
    (net (code "20") (name "/DIMMER3") (class "Default")
      (node (ref "D66") (pin "2") (pinfunction "MT2_2") (pintype "passive"))
      (node (ref "P12") (pin "4") (pinfunction "4_4") (pintype "passive"))
      (node (ref "R106") (pin "1") (pinfunction "1_1") (pintype "passive"))
      (node (ref "R124") (pin "2") (pinfunction "2_2") (pintype "passive"))
    )
    (net (code "21") (name "/DIMMER4") (class "Default")
      (node (ref "D68") (pin "2") (pinfunction "MT2_2") (pintype "passive"))
      (node (ref "P12") (pin "5") (pinfunction "5_5") (pintype "passive"))
      (node (ref "R107") (pin "1") (pinfunction "1_1") (pintype "passive"))
      (node (ref "R137") (pin "2") (pinfunction "2_2") (pintype "passive"))
    )
    (net (code "22") (name "/DIMMER5") (class "Default")
      (node (ref "D70") (pin "2") (pinfunction "MT2_2") (pintype "passive"))
      (node (ref "P12") (pin "6") (pinfunction "6_6") (pintype "passive"))
      (node (ref "R108") (pin "1") (pinfunction "1_1") (pintype "passive"))
      (node (ref "R150") (pin "2") (pinfunction "2_2") (pintype "passive"))
    )
    (net (code "23") (name "/DIMMER6") (class "Default")
      (node (ref "D72") (pin "2") (pinfunction "MT2_2") (pintype "passive"))
      (node (ref "P12") (pin "7") (pinfunction "7_7") (pintype "passive"))
      (node (ref "R119") (pin "1") (pinfunction "1_1") (pintype "passive"))
      (node (ref "R162") (pin "2") (pinfunction "2_2") (pintype "passive"))
    )
    (net (code "24") (name "/DIMMER7") (class "Default")
      (node (ref "D74") (pin "2") (pinfunction "MT2_2") (pintype "passive"))
      (node (ref "P12") (pin "8") (pinfunction "8_8") (pintype "passive"))
      (node (ref "R120") (pin "1") (pinfunction "1_1") (pintype "passive"))
      (node (ref "R172") (pin "2") (pinfunction "2_2") (pintype "passive"))
    )
    (net (code "25") (name "/DIMMER8") (class "Default")
      (node (ref "D61") (pin "2") (pinfunction "MT2_2") (pintype "passive"))
      (node (ref "P13") (pin "1") (pinfunction "1_1") (pintype "passive"))
      (node (ref "R131") (pin "1") (pinfunction "1_1") (pintype "passive"))
      (node (ref "R91") (pin "2") (pinfunction "2_2") (pintype "passive"))
    )
    (net (code "26") (name "/DIMMER9") (class "Default")
      (node (ref "D63") (pin "2") (pinfunction "MT2_2") (pintype "passive"))
      (node (ref "P13") (pin "2") (pinfunction "2_2") (pintype "passive"))
      (node (ref "R103") (pin "2") (pinfunction "2_2") (pintype "passive"))
      (node (ref "R132") (pin "1") (pinfunction "1_1") (pintype "passive"))
    )
    (net (code "27") (name "/DIMMER10") (class "Default")
      (node (ref "D65") (pin "2") (pinfunction "MT2_2") (pintype "passive"))
      (node (ref "P13") (pin "3") (pinfunction "3_3") (pintype "passive"))
      (node (ref "R116") (pin "2") (pinfunction "2_2") (pintype "passive"))
      (node (ref "R133") (pin "1") (pinfunction "1_1") (pintype "passive"))
    )
    (net (code "28") (name "/DIMMER11") (class "Default")
      (node (ref "D67") (pin "2") (pinfunction "MT2_2") (pintype "passive"))
      (node (ref "P13") (pin "4") (pinfunction "4_4") (pintype "passive"))
      (node (ref "R128") (pin "2") (pinfunction "2_2") (pintype "passive"))
      (node (ref "R144") (pin "1") (pinfunction "1_1") (pintype "passive"))
    )
    (net (code "29") (name "/DIMMER12") (class "Default")
      (node (ref "D69") (pin "2") (pinfunction "MT2_2") (pintype "passive"))
      (node (ref "P13") (pin "5") (pinfunction "5_5") (pintype "passive"))
      (node (ref "R141") (pin "2") (pinfunction "2_2") (pintype "passive"))
      (node (ref "R145") (pin "1") (pinfunction "1_1") (pintype "passive"))
    )
    (net (code "30") (name "/DIMMER13") (class "Default")
      (node (ref "D71") (pin "2") (pinfunction "MT2_2") (pintype "passive"))
      (node (ref "P13") (pin "6") (pinfunction "6_6") (pintype "passive"))
      (node (ref "R146") (pin "1") (pinfunction "1_1") (pintype "passive"))
      (node (ref "R154") (pin "2") (pinfunction "2_2") (pintype "passive"))
    )
    (net (code "31") (name "/DIMMER14") (class "Default")
      (node (ref "D73") (pin "2") (pinfunction "MT2_2") (pintype "passive"))
      (node (ref "P13") (pin "7") (pinfunction "7_7") (pintype "passive"))
      (node (ref "R157") (pin "1") (pinfunction "1_1") (pintype "passive"))
      (node (ref "R166") (pin "2") (pinfunction "2_2") (pintype "passive"))
    )
    (net (code "32") (name "/DIMMER15") (class "Default")
      (node (ref "D75") (pin "2") (pinfunction "MT2_2") (pintype "passive"))
      (node (ref "P13") (pin "8") (pinfunction "8_8") (pintype "passive"))
      (node (ref "R158") (pin "1") (pinfunction "1_1") (pintype "passive"))
      (node (ref "R176") (pin "2") (pinfunction "2_2") (pintype "passive"))
    )
    (net (code "33") (name "L1") (class "Default")
      (node (ref "C29") (pin "2") (pinfunction "2_2") (pintype "passive"))
      (node (ref "C30") (pin "1") (pinfunction "1_1") (pintype "passive"))
      (node (ref "C32") (pin "2") (pinfunction "2_2") (pintype "passive"))
      (node (ref "C33") (pin "2") (pinfunction "2_2") (pintype "passive"))
      (node (ref "C34") (pin "2") (pinfunction "2_2") (pintype "passive"))
      (node (ref "C35") (pin "1") (pinfunction "1_1") (pintype "passive"))
      (node (ref "C37") (pin "2") (pinfunction "2_2") (pintype "passive"))
      (node (ref "C38") (pin "2") (pinfunction "2_2") (pintype "passive"))
      (node (ref "C39") (pin "2") (pinfunction "2_2") (pintype "passive"))
      (node (ref "C40") (pin "1") (pinfunction "1_1") (pintype "passive"))
      (node (ref "C42") (pin "2") (pinfunction "2_2") (pintype "passive"))
      (node (ref "C44") (pin "1") (pinfunction "1_1") (pintype "passive"))
      (node (ref "C49") (pin "1") (pinfunction "1_1") (pintype "passive"))
      (node (ref "C54") (pin "1") (pinfunction "1_1") (pintype "passive"))
      (node (ref "C57") (pin "1") (pinfunction "1_1") (pintype "passive"))
      (node (ref "C59") (pin "1") (pinfunction "1_1") (pintype "passive"))
      (node (ref "D60") (pin "1") (pinfunction "MT1_1") (pintype "passive"))
      (node (ref "D62") (pin "1") (pinfunction "MT1_1") (pintype "passive"))
      (node (ref "D64") (pin "1") (pinfunction "MT1_1") (pintype "passive"))
      (node (ref "D66") (pin "1") (pinfunction "MT1_1") (pintype "passive"))
      (node (ref "D68") (pin "1") (pinfunction "MT1_1") (pintype "passive"))
      (node (ref "D70") (pin "1") (pinfunction "MT1_1") (pintype "passive"))
      (node (ref "D72") (pin "1") (pinfunction "MT1_1") (pintype "passive"))
      (node (ref "D74") (pin "1") (pinfunction "MT1_1") (pintype "passive"))
      (node (ref "P14") (pin "1") (pinfunction "1_1") (pintype "passive"))
    )
    (net (code "34") (name "L2") (class "Default")
      (node (ref "C31") (pin "1") (pinfunction "1_1") (pintype "passive"))
      (node (ref "C36") (pin "1") (pinfunction "1_1") (pintype "passive"))
      (node (ref "C41") (pin "1") (pinfunction "1_1") (pintype "passive"))
      (node (ref "C43") (pin "2") (pinfunction "2_2") (pintype "passive"))
      (node (ref "C45") (pin "1") (pinfunction "1_1") (pintype "passive"))
      (node (ref "C46") (pin "2") (pinfunction "2_2") (pintype "passive"))
      (node (ref "C47") (pin "2") (pinfunction "2_2") (pintype "passive"))
      (node (ref "C48") (pin "2") (pinfunction "2_2") (pintype "passive"))
      (node (ref "C50") (pin "1") (pinfunction "1_1") (pintype "passive"))
      (node (ref "C51") (pin "2") (pinfunction "2_2") (pintype "passive"))
      (node (ref "C52") (pin "2") (pinfunction "2_2") (pintype "passive"))
      (node (ref "C53") (pin "2") (pinfunction "2_2") (pintype "passive"))
      (node (ref "C55") (pin "1") (pinfunction "1_1") (pintype "passive"))
      (node (ref "C56") (pin "2") (pinfunction "2_2") (pintype "passive"))
      (node (ref "C58") (pin "1") (pinfunction "1_1") (pintype "passive"))
      (node (ref "C60") (pin "1") (pinfunction "1_1") (pintype "passive"))
      (node (ref "D61") (pin "1") (pinfunction "MT1_1") (pintype "passive"))
      (node (ref "D63") (pin "1") (pinfunction "MT1_1") (pintype "passive"))
      (node (ref "D65") (pin "1") (pinfunction "MT1_1") (pintype "passive"))
      (node (ref "D67") (pin "1") (pinfunction "MT1_1") (pintype "passive"))
      (node (ref "D69") (pin "1") (pinfunction "MT1_1") (pintype "passive"))
      (node (ref "D71") (pin "1") (pinfunction "MT1_1") (pintype "passive"))
      (node (ref "D73") (pin "1") (pinfunction "MT1_1") (pintype "passive"))
      (node (ref "D75") (pin "1") (pinfunction "MT1_1") (pintype "passive"))
      (node (ref "P15") (pin "1") (pinfunction "1_1") (pintype "passive"))
    )
    (net (code "35") (name "N1") (class "Default")
      (node (ref "P14") (pin "2") (pinfunction "2_2") (pintype "passive"))
    )
    (net (code "36") (name "N2") (class "Default")
      (node (ref "P15") (pin "2") (pinfunction "2_2") (pintype "passive"))
    )
    (net (code "37") (name "Net-(C29-Pad1)") (class "Default")
      (node (ref "C29") (pin "1") (pinfunction "1_1") (pintype "passive"))
      (node (ref "R83") (pin "2") (pinfunction "2_2") (pintype "passive"))
    )
    (net (code "38") (name "Net-(C30-Pad2)") (class "Default")
      (node (ref "C30") (pin "2") (pinfunction "2_2") (pintype "passive"))
      (node (ref "R85") (pin "2") (pinfunction "2_2") (pintype "passive"))
      (node (ref "R86") (pin "1") (pinfunction "1_1") (pintype "passive"))
    )
    (net (code "39") (name "Net-(C31-Pad2)") (class "Default")
      (node (ref "C31") (pin "2") (pinfunction "2_2") (pintype "passive"))
      (node (ref "R89") (pin "2") (pinfunction "2_2") (pintype "passive"))
      (node (ref "R90") (pin "1") (pinfunction "1_1") (pintype "passive"))
    )
    (net (code "40") (name "Net-(C32-Pad1)") (class "Default")
      (node (ref "C32") (pin "1") (pinfunction "1_1") (pintype "passive"))
      (node (ref "R94") (pin "2") (pinfunction "2_2") (pintype "passive"))
    )
    (net (code "41") (name "Net-(C33-Pad1)") (class "Default")
      (node (ref "C33") (pin "1") (pinfunction "1_1") (pintype "passive"))
      (node (ref "R95") (pin "2") (pinfunction "2_2") (pintype "passive"))
    )
    (net (code "42") (name "Net-(C34-Pad1)") (class "Default")
      (node (ref "C34") (pin "1") (pinfunction "1_1") (pintype "passive"))
      (node (ref "R106") (pin "2") (pinfunction "2_2") (pintype "passive"))
    )
    (net (code "43") (name "Net-(C35-Pad2)") (class "Default")
      (node (ref "C35") (pin "2") (pinfunction "2_2") (pintype "passive"))
      (node (ref "R97") (pin "2") (pinfunction "2_2") (pintype "passive"))
      (node (ref "R98") (pin "1") (pinfunction "1_1") (pintype "passive"))
    )
    (net (code "44") (name "Net-(C36-Pad2)") (class "Default")
      (node (ref "C36") (pin "2") (pinfunction "2_2") (pintype "passive"))
      (node (ref "R101") (pin "2") (pinfunction "2_2") (pintype "passive"))
      (node (ref "R102") (pin "1") (pinfunction "1_1") (pintype "passive"))
    )
    (net (code "45") (name "Net-(C37-Pad1)") (class "Default")
      (node (ref "C37") (pin "1") (pinfunction "1_1") (pintype "passive"))
      (node (ref "R107") (pin "2") (pinfunction "2_2") (pintype "passive"))
    )
    (net (code "46") (name "Net-(C38-Pad1)") (class "Default")
      (node (ref "C38") (pin "1") (pinfunction "1_1") (pintype "passive"))
      (node (ref "R108") (pin "2") (pinfunction "2_2") (pintype "passive"))
    )
    (net (code "47") (name "Net-(C39-Pad1)") (class "Default")
      (node (ref "C39") (pin "1") (pinfunction "1_1") (pintype "passive"))
      (node (ref "R119") (pin "2") (pinfunction "2_2") (pintype "passive"))
    )
    (net (code "48") (name "Net-(C40-Pad2)") (class "Default")
      (node (ref "C40") (pin "2") (pinfunction "2_2") (pintype "passive"))
      (node (ref "R110") (pin "2") (pinfunction "2_2") (pintype "passive"))
      (node (ref "R111") (pin "1") (pinfunction "1_1") (pintype "passive"))
    )
    (net (code "49") (name "Net-(C41-Pad2)") (class "Default")
      (node (ref "C41") (pin "2") (pinfunction "2_2") (pintype "passive"))
      (node (ref "R114") (pin "2") (pinfunction "2_2") (pintype "passive"))
      (node (ref "R115") (pin "1") (pinfunction "1_1") (pintype "passive"))
    )
    (net (code "50") (name "Net-(C42-Pad1)") (class "Default")
      (node (ref "C42") (pin "1") (pinfunction "1_1") (pintype "passive"))
      (node (ref "R120") (pin "2") (pinfunction "2_2") (pintype "passive"))
    )
    (net (code "51") (name "Net-(C43-Pad1)") (class "Default")
      (node (ref "C43") (pin "1") (pinfunction "1_1") (pintype "passive"))
      (node (ref "R131") (pin "2") (pinfunction "2_2") (pintype "passive"))
    )
    (net (code "52") (name "Net-(C44-Pad2)") (class "Default")
      (node (ref "C44") (pin "2") (pinfunction "2_2") (pintype "passive"))
      (node (ref "R122") (pin "2") (pinfunction "2_2") (pintype "passive"))
      (node (ref "R123") (pin "1") (pinfunction "1_1") (pintype "passive"))
    )
    (net (code "53") (name "Net-(C45-Pad2)") (class "Default")
      (node (ref "C45") (pin "2") (pinfunction "2_2") (pintype "passive"))
      (node (ref "R126") (pin "2") (pinfunction "2_2") (pintype "passive"))
      (node (ref "R127") (pin "1") (pinfunction "1_1") (pintype "passive"))
    )
    (net (code "54") (name "Net-(C46-Pad1)") (class "Default")
      (node (ref "C46") (pin "1") (pinfunction "1_1") (pintype "passive"))
      (node (ref "R132") (pin "2") (pinfunction "2_2") (pintype "passive"))
    )
    (net (code "55") (name "Net-(C47-Pad1)") (class "Default")
      (node (ref "C47") (pin "1") (pinfunction "1_1") (pintype "passive"))
      (node (ref "R133") (pin "2") (pinfunction "2_2") (pintype "passive"))
    )
    (net (code "56") (name "Net-(C48-Pad1)") (class "Default")
      (node (ref "C48") (pin "1") (pinfunction "1_1") (pintype "passive"))
      (node (ref "R144") (pin "2") (pinfunction "2_2") (pintype "passive"))
    )
    (net (code "57") (name "Net-(C49-Pad2)") (class "Default")
      (node (ref "C49") (pin "2") (pinfunction "2_2") (pintype "passive"))
      (node (ref "R135") (pin "2") (pinfunction "2_2") (pintype "passive"))
      (node (ref "R136") (pin "1") (pinfunction "1_1") (pintype "passive"))
    )
    (net (code "58") (name "Net-(C50-Pad2)") (class "Default")
      (node (ref "C50") (pin "2") (pinfunction "2_2") (pintype "passive"))
      (node (ref "R139") (pin "2") (pinfunction "2_2") (pintype "passive"))
      (node (ref "R140") (pin "1") (pinfunction "1_1") (pintype "passive"))
    )
    (net (code "59") (name "Net-(C51-Pad1)") (class "Default")
      (node (ref "C51") (pin "1") (pinfunction "1_1") (pintype "passive"))
      (node (ref "R145") (pin "2") (pinfunction "2_2") (pintype "passive"))
    )
    (net (code "60") (name "Net-(C52-Pad1)") (class "Default")
      (node (ref "C52") (pin "1") (pinfunction "1_1") (pintype "passive"))
      (node (ref "R146") (pin "2") (pinfunction "2_2") (pintype "passive"))
    )
    (net (code "61") (name "Net-(C53-Pad1)") (class "Default")
      (node (ref "C53") (pin "1") (pinfunction "1_1") (pintype "passive"))
      (node (ref "R157") (pin "2") (pinfunction "2_2") (pintype "passive"))
    )
    (net (code "62") (name "Net-(C54-Pad2)") (class "Default")
      (node (ref "C54") (pin "2") (pinfunction "2_2") (pintype "passive"))
      (node (ref "R148") (pin "2") (pinfunction "2_2") (pintype "passive"))
      (node (ref "R149") (pin "1") (pinfunction "1_1") (pintype "passive"))
    )
    (net (code "63") (name "Net-(C55-Pad2)") (class "Default")
      (node (ref "C55") (pin "2") (pinfunction "2_2") (pintype "passive"))
      (node (ref "R152") (pin "2") (pinfunction "2_2") (pintype "passive"))
      (node (ref "R153") (pin "1") (pinfunction "1_1") (pintype "passive"))
    )
    (net (code "64") (name "Net-(C56-Pad1)") (class "Default")
      (node (ref "C56") (pin "1") (pinfunction "1_1") (pintype "passive"))
      (node (ref "R158") (pin "2") (pinfunction "2_2") (pintype "passive"))
    )
    (net (code "65") (name "Net-(C57-Pad2)") (class "Default")
      (node (ref "C57") (pin "2") (pinfunction "2_2") (pintype "passive"))
      (node (ref "R160") (pin "2") (pinfunction "2_2") (pintype "passive"))
      (node (ref "R161") (pin "1") (pinfunction "1_1") (pintype "passive"))
    )
    (net (code "66") (name "Net-(C58-Pad2)") (class "Default")
      (node (ref "C58") (pin "2") (pinfunction "2_2") (pintype "passive"))
      (node (ref "R164") (pin "2") (pinfunction "2_2") (pintype "passive"))
      (node (ref "R165") (pin "1") (pinfunction "1_1") (pintype "passive"))
    )
    (net (code "67") (name "Net-(C59-Pad2)") (class "Default")
      (node (ref "C59") (pin "2") (pinfunction "2_2") (pintype "passive"))
      (node (ref "R170") (pin "2") (pinfunction "2_2") (pintype "passive"))
      (node (ref "R171") (pin "1") (pinfunction "1_1") (pintype "passive"))
    )
    (net (code "68") (name "Net-(C60-Pad2)") (class "Default")
      (node (ref "C60") (pin "2") (pinfunction "2_2") (pintype "passive"))
      (node (ref "R174") (pin "2") (pinfunction "2_2") (pintype "passive"))
      (node (ref "R175") (pin "1") (pinfunction "1_1") (pintype "passive"))
    )
    (net (code "69") (name "Net-(D60-G)") (class "Default")
      (node (ref "D60") (pin "3") (pinfunction "G_3") (pintype "passive"))
      (node (ref "U15") (pin "4") (pinfunction "4_4") (pintype "passive"))
    )
    (net (code "70") (name "Net-(D61-G)") (class "Default")
      (node (ref "D61") (pin "3") (pinfunction "G_3") (pintype "passive"))
      (node (ref "U16") (pin "4") (pinfunction "4_4") (pintype "passive"))
    )
    (net (code "71") (name "Net-(D62-G)") (class "Default")
      (node (ref "D62") (pin "3") (pinfunction "G_3") (pintype "passive"))
      (node (ref "U17") (pin "4") (pinfunction "4_4") (pintype "passive"))
    )
    (net (code "72") (name "Net-(D63-G)") (class "Default")
      (node (ref "D63") (pin "3") (pinfunction "G_3") (pintype "passive"))
      (node (ref "U18") (pin "4") (pinfunction "4_4") (pintype "passive"))
    )
    (net (code "73") (name "Net-(D64-G)") (class "Default")
      (node (ref "D64") (pin "3") (pinfunction "G_3") (pintype "passive"))
      (node (ref "U19") (pin "4") (pinfunction "4_4") (pintype "passive"))
    )
    (net (code "74") (name "Net-(D65-G)") (class "Default")
      (node (ref "D65") (pin "3") (pinfunction "G_3") (pintype "passive"))
      (node (ref "U20") (pin "4") (pinfunction "4_4") (pintype "passive"))
    )
    (net (code "75") (name "Net-(D66-G)") (class "Default")
      (node (ref "D66") (pin "3") (pinfunction "G_3") (pintype "passive"))
      (node (ref "U21") (pin "4") (pinfunction "4_4") (pintype "passive"))
    )
    (net (code "76") (name "Net-(D67-G)") (class "Default")
      (node (ref "D67") (pin "3") (pinfunction "G_3") (pintype "passive"))
      (node (ref "U22") (pin "4") (pinfunction "4_4") (pintype "passive"))
    )
    (net (code "77") (name "Net-(D68-G)") (class "Default")
      (node (ref "D68") (pin "3") (pinfunction "G_3") (pintype "passive"))
      (node (ref "U23") (pin "4") (pinfunction "4_4") (pintype "passive"))
    )
    (net (code "78") (name "Net-(D69-G)") (class "Default")
      (node (ref "D69") (pin "3") (pinfunction "G_3") (pintype "passive"))
      (node (ref "U24") (pin "4") (pinfunction "4_4") (pintype "passive"))
    )
    (net (code "79") (name "Net-(D70-G)") (class "Default")
      (node (ref "D70") (pin "3") (pinfunction "G_3") (pintype "passive"))
      (node (ref "U25") (pin "4") (pinfunction "4_4") (pintype "passive"))
    )
    (net (code "80") (name "Net-(D71-G)") (class "Default")
      (node (ref "D71") (pin "3") (pinfunction "G_3") (pintype "passive"))
      (node (ref "U26") (pin "4") (pinfunction "4_4") (pintype "passive"))
    )
    (net (code "81") (name "Net-(D72-G)") (class "Default")
      (node (ref "D72") (pin "3") (pinfunction "G_3") (pintype "passive"))
      (node (ref "U27") (pin "4") (pinfunction "4_4") (pintype "passive"))
    )
    (net (code "82") (name "Net-(D73-G)") (class "Default")
      (node (ref "D73") (pin "3") (pinfunction "G_3") (pintype "passive"))
      (node (ref "U28") (pin "4") (pinfunction "4_4") (pintype "passive"))
    )
    (net (code "83") (name "Net-(D74-G)") (class "Default")
      (node (ref "D74") (pin "3") (pinfunction "G_3") (pintype "passive"))
      (node (ref "U29") (pin "4") (pinfunction "4_4") (pintype "passive"))
    )
    (net (code "84") (name "Net-(D75-G)") (class "Default")
      (node (ref "D75") (pin "3") (pinfunction "G_3") (pintype "passive"))
      (node (ref "U30") (pin "4") (pinfunction "4_4") (pintype "passive"))
    )
    (net (code "85") (name "Net-(R84-Pad1)") (class "Default")
      (node (ref "R84") (pin "1") (pinfunction "1_1") (pintype "passive"))
      (node (ref "U15") (pin "6") (pinfunction "6_6") (pintype "passive"))
    )
    (net (code "86") (name "Net-(R84-Pad2)") (class "Default")
      (node (ref "R84") (pin "2") (pinfunction "2_2") (pintype "passive"))
      (node (ref "R85") (pin "1") (pinfunction "1_1") (pintype "passive"))
    )
    (net (code "87") (name "Net-(R86-Pad2)") (class "Default")
      (node (ref "R86") (pin "2") (pinfunction "2_2") (pintype "passive"))
      (node (ref "R87") (pin "1") (pinfunction "1_1") (pintype "passive"))
    )
    (net (code "88") (name "Net-(R88-Pad1)") (class "Default")
      (node (ref "R88") (pin "1") (pinfunction "1_1") (pintype "passive"))
      (node (ref "U16") (pin "6") (pinfunction "6_6") (pintype "passive"))
    )
    (net (code "89") (name "Net-(R88-Pad2)") (class "Default")
      (node (ref "R88") (pin "2") (pinfunction "2_2") (pintype "passive"))
      (node (ref "R89") (pin "1") (pinfunction "1_1") (pintype "passive"))
    )
    (net (code "90") (name "Net-(R90-Pad2)") (class "Default")
      (node (ref "R90") (pin "2") (pinfunction "2_2") (pintype "passive"))
      (node (ref "R91") (pin "1") (pinfunction "1_1") (pintype "passive"))
    )
    (net (code "91") (name "Net-(R92-Pad2)") (class "Default")
      (node (ref "R92") (pin "2") (pinfunction "2_2") (pintype "passive"))
      (node (ref "U15") (pin "1") (pinfunction "1_1") (pintype "passive"))
    )
    (net (code "92") (name "Net-(R93-Pad2)") (class "Default")
      (node (ref "R93") (pin "2") (pinfunction "2_2") (pintype "passive"))
      (node (ref "U16") (pin "1") (pinfunction "1_1") (pintype "passive"))
    )
    (net (code "93") (name "Net-(R96-Pad1)") (class "Default")
      (node (ref "R96") (pin "1") (pinfunction "1_1") (pintype "passive"))
      (node (ref "U17") (pin "6") (pinfunction "6_6") (pintype "passive"))
    )
    (net (code "94") (name "Net-(R96-Pad2)") (class "Default")
      (node (ref "R96") (pin "2") (pinfunction "2_2") (pintype "passive"))
      (node (ref "R97") (pin "1") (pinfunction "1_1") (pintype "passive"))
    )
    (net (code "95") (name "Net-(R98-Pad2)") (class "Default")
      (node (ref "R98") (pin "2") (pinfunction "2_2") (pintype "passive"))
      (node (ref "R99") (pin "1") (pinfunction "1_1") (pintype "passive"))
    )
    (net (code "96") (name "Net-(R100-Pad1)") (class "Default")
      (node (ref "R100") (pin "1") (pinfunction "1_1") (pintype "passive"))
      (node (ref "U18") (pin "6") (pinfunction "6_6") (pintype "passive"))
    )
    (net (code "97") (name "Net-(R100-Pad2)") (class "Default")
      (node (ref "R100") (pin "2") (pinfunction "2_2") (pintype "passive"))
      (node (ref "R101") (pin "1") (pinfunction "1_1") (pintype "passive"))
    )
    (net (code "98") (name "Net-(R102-Pad2)") (class "Default")
      (node (ref "R102") (pin "2") (pinfunction "2_2") (pintype "passive"))
      (node (ref "R103") (pin "1") (pinfunction "1_1") (pintype "passive"))
    )
    (net (code "99") (name "Net-(R104-Pad2)") (class "Default")
      (node (ref "R104") (pin "2") (pinfunction "2_2") (pintype "passive"))
      (node (ref "U17") (pin "1") (pinfunction "1_1") (pintype "passive"))
    )
    (net (code "100") (name "Net-(R105-Pad2)") (class "Default")
      (node (ref "R105") (pin "2") (pinfunction "2_2") (pintype "passive"))
      (node (ref "U18") (pin "1") (pinfunction "1_1") (pintype "passive"))
    )
    (net (code "101") (name "Net-(R109-Pad1)") (class "Default")
      (node (ref "R109") (pin "1") (pinfunction "1_1") (pintype "passive"))
      (node (ref "U19") (pin "6") (pinfunction "6_6") (pintype "passive"))
    )
    (net (code "102") (name "Net-(R109-Pad2)") (class "Default")
      (node (ref "R109") (pin "2") (pinfunction "2_2") (pintype "passive"))
      (node (ref "R110") (pin "1") (pinfunction "1_1") (pintype "passive"))
    )
    (net (code "103") (name "Net-(R111-Pad2)") (class "Default")
      (node (ref "R111") (pin "2") (pinfunction "2_2") (pintype "passive"))
      (node (ref "R112") (pin "1") (pinfunction "1_1") (pintype "passive"))
    )
    (net (code "104") (name "Net-(R113-Pad1)") (class "Default")
      (node (ref "R113") (pin "1") (pinfunction "1_1") (pintype "passive"))
      (node (ref "U20") (pin "6") (pinfunction "6_6") (pintype "passive"))
    )
    (net (code "105") (name "Net-(R113-Pad2)") (class "Default")
      (node (ref "R113") (pin "2") (pinfunction "2_2") (pintype "passive"))
      (node (ref "R114") (pin "1") (pinfunction "1_1") (pintype "passive"))
    )
    (net (code "106") (name "Net-(R115-Pad2)") (class "Default")
      (node (ref "R115") (pin "2") (pinfunction "2_2") (pintype "passive"))
      (node (ref "R116") (pin "1") (pinfunction "1_1") (pintype "passive"))
    )
    (net (code "107") (name "Net-(R117-Pad2)") (class "Default")
      (node (ref "R117") (pin "2") (pinfunction "2_2") (pintype "passive"))
      (node (ref "U19") (pin "1") (pinfunction "1_1") (pintype "passive"))
    )
    (net (code "108") (name "Net-(R118-Pad2)") (class "Default")
      (node (ref "R118") (pin "2") (pinfunction "2_2") (pintype "passive"))
      (node (ref "U20") (pin "1") (pinfunction "1_1") (pintype "passive"))
    )
    (net (code "109") (name "Net-(R121-Pad1)") (class "Default")
      (node (ref "R121") (pin "1") (pinfunction "1_1") (pintype "passive"))
      (node (ref "U21") (pin "6") (pinfunction "6_6") (pintype "passive"))
    )
    (net (code "110") (name "Net-(R121-Pad2)") (class "Default")
      (node (ref "R121") (pin "2") (pinfunction "2_2") (pintype "passive"))
      (node (ref "R122") (pin "1") (pinfunction "1_1") (pintype "passive"))
    )
    (net (code "111") (name "Net-(R123-Pad2)") (class "Default")
      (node (ref "R123") (pin "2") (pinfunction "2_2") (pintype "passive"))
      (node (ref "R124") (pin "1") (pinfunction "1_1") (pintype "passive"))
    )
    (net (code "112") (name "Net-(R125-Pad1)") (class "Default")
      (node (ref "R125") (pin "1") (pinfunction "1_1") (pintype "passive"))
      (node (ref "U22") (pin "6") (pinfunction "6_6") (pintype "passive"))
    )
    (net (code "113") (name "Net-(R125-Pad2)") (class "Default")
      (node (ref "R125") (pin "2") (pinfunction "2_2") (pintype "passive"))
      (node (ref "R126") (pin "1") (pinfunction "1_1") (pintype "passive"))
    )
    (net (code "114") (name "Net-(R127-Pad2)") (class "Default")
      (node (ref "R127") (pin "2") (pinfunction "2_2") (pintype "passive"))
      (node (ref "R128") (pin "1") (pinfunction "1_1") (pintype "passive"))
    )
    (net (code "115") (name "Net-(R129-Pad2)") (class "Default")
      (node (ref "R129") (pin "2") (pinfunction "2_2") (pintype "passive"))
      (node (ref "U21") (pin "1") (pinfunction "1_1") (pintype "passive"))
    )
    (net (code "116") (name "Net-(R130-Pad2)") (class "Default")
      (node (ref "R130") (pin "2") (pinfunction "2_2") (pintype "passive"))
      (node (ref "U22") (pin "1") (pinfunction "1_1") (pintype "passive"))
    )
    (net (code "117") (name "Net-(R134-Pad1)") (class "Default")
      (node (ref "R134") (pin "1") (pinfunction "1_1") (pintype "passive"))
      (node (ref "U23") (pin "6") (pinfunction "6_6") (pintype "passive"))
    )
    (net (code "118") (name "Net-(R134-Pad2)") (class "Default")
      (node (ref "R134") (pin "2") (pinfunction "2_2") (pintype "passive"))
      (node (ref "R135") (pin "1") (pinfunction "1_1") (pintype "passive"))
    )
    (net (code "119") (name "Net-(R136-Pad2)") (class "Default")
      (node (ref "R136") (pin "2") (pinfunction "2_2") (pintype "passive"))
      (node (ref "R137") (pin "1") (pinfunction "1_1") (pintype "passive"))
    )
    (net (code "120") (name "Net-(R138-Pad1)") (class "Default")
      (node (ref "R138") (pin "1") (pinfunction "1_1") (pintype "passive"))
      (node (ref "U24") (pin "6") (pinfunction "6_6") (pintype "passive"))
    )
    (net (code "121") (name "Net-(R138-Pad2)") (class "Default")
      (node (ref "R138") (pin "2") (pinfunction "2_2") (pintype "passive"))
      (node (ref "R139") (pin "1") (pinfunction "1_1") (pintype "passive"))
    )
    (net (code "122") (name "Net-(R140-Pad2)") (class "Default")
      (node (ref "R140") (pin "2") (pinfunction "2_2") (pintype "passive"))
      (node (ref "R141") (pin "1") (pinfunction "1_1") (pintype "passive"))
    )
    (net (code "123") (name "Net-(R142-Pad2)") (class "Default")
      (node (ref "R142") (pin "2") (pinfunction "2_2") (pintype "passive"))
      (node (ref "U23") (pin "1") (pinfunction "1_1") (pintype "passive"))
    )
    (net (code "124") (name "Net-(R143-Pad2)") (class "Default")
      (node (ref "R143") (pin "2") (pinfunction "2_2") (pintype "passive"))
      (node (ref "U24") (pin "1") (pinfunction "1_1") (pintype "passive"))
    )
    (net (code "125") (name "Net-(R147-Pad1)") (class "Default")
      (node (ref "R147") (pin "1") (pinfunction "1_1") (pintype "passive"))
      (node (ref "U25") (pin "6") (pinfunction "6_6") (pintype "passive"))
    )
    (net (code "126") (name "Net-(R147-Pad2)") (class "Default")
      (node (ref "R147") (pin "2") (pinfunction "2_2") (pintype "passive"))
      (node (ref "R148") (pin "1") (pinfunction "1_1") (pintype "passive"))
    )
    (net (code "127") (name "Net-(R149-Pad2)") (class "Default")
      (node (ref "R149") (pin "2") (pinfunction "2_2") (pintype "passive"))
      (node (ref "R150") (pin "1") (pinfunction "1_1") (pintype "passive"))
    )
    (net (code "128") (name "Net-(R151-Pad1)") (class "Default")
      (node (ref "R151") (pin "1") (pinfunction "1_1") (pintype "passive"))
      (node (ref "U26") (pin "6") (pinfunction "6_6") (pintype "passive"))
    )
    (net (code "129") (name "Net-(R151-Pad2)") (class "Default")
      (node (ref "R151") (pin "2") (pinfunction "2_2") (pintype "passive"))
      (node (ref "R152") (pin "1") (pinfunction "1_1") (pintype "passive"))
    )
    (net (code "130") (name "Net-(R153-Pad2)") (class "Default")
      (node (ref "R153") (pin "2") (pinfunction "2_2") (pintype "passive"))
      (node (ref "R154") (pin "1") (pinfunction "1_1") (pintype "passive"))
    )
    (net (code "131") (name "Net-(R155-Pad2)") (class "Default")
      (node (ref "R155") (pin "2") (pinfunction "2_2") (pintype "passive"))
      (node (ref "U25") (pin "1") (pinfunction "1_1") (pintype "passive"))
    )
    (net (code "132") (name "Net-(R156-Pad2)") (class "Default")
      (node (ref "R156") (pin "2") (pinfunction "2_2") (pintype "passive"))
      (node (ref "U26") (pin "1") (pinfunction "1_1") (pintype "passive"))
    )
    (net (code "133") (name "Net-(R159-Pad1)") (class "Default")
      (node (ref "R159") (pin "1") (pinfunction "1_1") (pintype "passive"))
      (node (ref "U27") (pin "6") (pinfunction "6_6") (pintype "passive"))
    )
    (net (code "134") (name "Net-(R159-Pad2)") (class "Default")
      (node (ref "R159") (pin "2") (pinfunction "2_2") (pintype "passive"))
      (node (ref "R160") (pin "1") (pinfunction "1_1") (pintype "passive"))
    )
    (net (code "135") (name "Net-(R161-Pad2)") (class "Default")
      (node (ref "R161") (pin "2") (pinfunction "2_2") (pintype "passive"))
      (node (ref "R162") (pin "1") (pinfunction "1_1") (pintype "passive"))
    )
    (net (code "136") (name "Net-(R163-Pad1)") (class "Default")
      (node (ref "R163") (pin "1") (pinfunction "1_1") (pintype "passive"))
      (node (ref "U28") (pin "6") (pinfunction "6_6") (pintype "passive"))
    )
    (net (code "137") (name "Net-(R163-Pad2)") (class "Default")
      (node (ref "R163") (pin "2") (pinfunction "2_2") (pintype "passive"))
      (node (ref "R164") (pin "1") (pinfunction "1_1") (pintype "passive"))
    )
    (net (code "138") (name "Net-(R165-Pad2)") (class "Default")
      (node (ref "R165") (pin "2") (pinfunction "2_2") (pintype "passive"))
      (node (ref "R166") (pin "1") (pinfunction "1_1") (pintype "passive"))
    )
    (net (code "139") (name "Net-(R167-Pad2)") (class "Default")
      (node (ref "R167") (pin "2") (pinfunction "2_2") (pintype "passive"))
      (node (ref "U27") (pin "1") (pinfunction "1_1") (pintype "passive"))
    )
    (net (code "140") (name "Net-(R168-Pad2)") (class "Default")
      (node (ref "R168") (pin "2") (pinfunction "2_2") (pintype "passive"))
      (node (ref "U28") (pin "1") (pinfunction "1_1") (pintype "passive"))
    )
    (net (code "141") (name "Net-(R169-Pad1)") (class "Default")
      (node (ref "R169") (pin "1") (pinfunction "1_1") (pintype "passive"))
      (node (ref "U29") (pin "6") (pinfunction "6_6") (pintype "passive"))
    )
    (net (code "142") (name "Net-(R169-Pad2)") (class "Default")
      (node (ref "R169") (pin "2") (pinfunction "2_2") (pintype "passive"))
      (node (ref "R170") (pin "1") (pinfunction "1_1") (pintype "passive"))
    )
    (net (code "143") (name "Net-(R171-Pad2)") (class "Default")
      (node (ref "R171") (pin "2") (pinfunction "2_2") (pintype "passive"))
      (node (ref "R172") (pin "1") (pinfunction "1_1") (pintype "passive"))
    )
    (net (code "144") (name "Net-(R173-Pad1)") (class "Default")
      (node (ref "R173") (pin "1") (pinfunction "1_1") (pintype "passive"))
      (node (ref "U30") (pin "6") (pinfunction "6_6") (pintype "passive"))
    )
    (net (code "145") (name "Net-(R173-Pad2)") (class "Default")
      (node (ref "R173") (pin "2") (pinfunction "2_2") (pintype "passive"))
      (node (ref "R174") (pin "1") (pinfunction "1_1") (pintype "passive"))
    )
    (net (code "146") (name "Net-(R175-Pad2)") (class "Default")
      (node (ref "R175") (pin "2") (pinfunction "2_2") (pintype "passive"))
      (node (ref "R176") (pin "1") (pinfunction "1_1") (pintype "passive"))
    )
    (net (code "147") (name "Net-(R177-Pad2)") (class "Default")
      (node (ref "R177") (pin "2") (pinfunction "2_2") (pintype "passive"))
      (node (ref "U29") (pin "1") (pinfunction "1_1") (pintype "passive"))
    )
    (net (code "148") (name "Net-(R178-Pad2)") (class "Default")
      (node (ref "R178") (pin "2") (pinfunction "2_2") (pintype "passive"))
      (node (ref "U30") (pin "1") (pinfunction "1_1") (pintype "passive"))
    )
    (net (code "149") (name "VSS") (class "Default")
      (node (ref "U15") (pin "2") (pinfunction "2_2") (pintype "passive"))
      (node (ref "U16") (pin "2") (pinfunction "2_2") (pintype "passive"))
      (node (ref "U17") (pin "2") (pinfunction "2_2") (pintype "passive"))
      (node (ref "U18") (pin "2") (pinfunction "2_2") (pintype "passive"))
      (node (ref "U19") (pin "2") (pinfunction "2_2") (pintype "passive"))
      (node (ref "U20") (pin "2") (pinfunction "2_2") (pintype "passive"))
      (node (ref "U21") (pin "2") (pinfunction "2_2") (pintype "passive"))
      (node (ref "U22") (pin "2") (pinfunction "2_2") (pintype "passive"))
      (node (ref "U23") (pin "2") (pinfunction "2_2") (pintype "passive"))
      (node (ref "U24") (pin "2") (pinfunction "2_2") (pintype "passive"))
      (node (ref "U25") (pin "2") (pinfunction "2_2") (pintype "passive"))
      (node (ref "U26") (pin "2") (pinfunction "2_2") (pintype "passive"))
      (node (ref "U27") (pin "2") (pinfunction "2_2") (pintype "passive"))
      (node (ref "U28") (pin "2") (pinfunction "2_2") (pintype "passive"))
      (node (ref "U29") (pin "2") (pinfunction "2_2") (pintype "passive"))
      (node (ref "U30") (pin "2") (pinfunction "2_2") (pintype "passive"))
    )
    (net (code "150") (name "unconnected-(U15-Pad3)") (class "Default")
      (node (ref "U15") (pin "3") (pinfunction "3_3") (pintype "passive"))
    )
    (net (code "151") (name "unconnected-(U15-Pad5)") (class "Default")
      (node (ref "U15") (pin "5") (pinfunction "5_5") (pintype "passive"))
    )
    (net (code "152") (name "unconnected-(U16-Pad3)") (class "Default")
      (node (ref "U16") (pin "3") (pinfunction "3_3") (pintype "passive"))
    )
    (net (code "153") (name "unconnected-(U16-Pad5)") (class "Default")
      (node (ref "U16") (pin "5") (pinfunction "5_5") (pintype "passive"))
    )
    (net (code "154") (name "unconnected-(U17-Pad3)") (class "Default")
      (node (ref "U17") (pin "3") (pinfunction "3_3") (pintype "passive"))
    )
    (net (code "155") (name "unconnected-(U17-Pad5)") (class "Default")
      (node (ref "U17") (pin "5") (pinfunction "5_5") (pintype "passive"))
    )
    (net (code "156") (name "unconnected-(U18-Pad3)") (class "Default")
      (node (ref "U18") (pin "3") (pinfunction "3_3") (pintype "passive"))
    )
    (net (code "157") (name "unconnected-(U18-Pad5)") (class "Default")
      (node (ref "U18") (pin "5") (pinfunction "5_5") (pintype "passive"))
    )
    (net (code "158") (name "unconnected-(U19-Pad3)") (class "Default")
      (node (ref "U19") (pin "3") (pinfunction "3_3") (pintype "passive"))
    )
    (net (code "159") (name "unconnected-(U19-Pad5)") (class "Default")
      (node (ref "U19") (pin "5") (pinfunction "5_5") (pintype "passive"))
    )
    (net (code "160") (name "unconnected-(U20-Pad3)") (class "Default")
      (node (ref "U20") (pin "3") (pinfunction "3_3") (pintype "passive"))
    )
    (net (code "161") (name "unconnected-(U20-Pad5)") (class "Default")
      (node (ref "U20") (pin "5") (pinfunction "5_5") (pintype "passive"))
    )
    (net (code "162") (name "unconnected-(U21-Pad3)") (class "Default")
      (node (ref "U21") (pin "3") (pinfunction "3_3") (pintype "passive"))
    )
    (net (code "163") (name "unconnected-(U21-Pad5)") (class "Default")
      (node (ref "U21") (pin "5") (pinfunction "5_5") (pintype "passive"))
    )
    (net (code "164") (name "unconnected-(U22-Pad3)") (class "Default")
      (node (ref "U22") (pin "3") (pinfunction "3_3") (pintype "passive"))
    )
    (net (code "165") (name "unconnected-(U22-Pad5)") (class "Default")
      (node (ref "U22") (pin "5") (pinfunction "5_5") (pintype "passive"))
    )
    (net (code "166") (name "unconnected-(U23-Pad3)") (class "Default")
      (node (ref "U23") (pin "3") (pinfunction "3_3") (pintype "passive"))
    )
    (net (code "167") (name "unconnected-(U23-Pad5)") (class "Default")
      (node (ref "U23") (pin "5") (pinfunction "5_5") (pintype "passive"))
    )
    (net (code "168") (name "unconnected-(U24-Pad3)") (class "Default")
      (node (ref "U24") (pin "3") (pinfunction "3_3") (pintype "passive"))
    )
    (net (code "169") (name "unconnected-(U24-Pad5)") (class "Default")
      (node (ref "U24") (pin "5") (pinfunction "5_5") (pintype "passive"))
    )
    (net (code "170") (name "unconnected-(U25-Pad3)") (class "Default")
      (node (ref "U25") (pin "3") (pinfunction "3_3") (pintype "passive"))
    )
    (net (code "171") (name "unconnected-(U25-Pad5)") (class "Default")
      (node (ref "U25") (pin "5") (pinfunction "5_5") (pintype "passive"))
    )
    (net (code "172") (name "unconnected-(U26-Pad3)") (class "Default")
      (node (ref "U26") (pin "3") (pinfunction "3_3") (pintype "passive"))
    )
    (net (code "173") (name "unconnected-(U26-Pad5)") (class "Default")
      (node (ref "U26") (pin "5") (pinfunction "5_5") (pintype "passive"))
    )
    (net (code "174") (name "unconnected-(U27-Pad3)") (class "Default")
      (node (ref "U27") (pin "3") (pinfunction "3_3") (pintype "passive"))
    )
    (net (code "175") (name "unconnected-(U27-Pad5)") (class "Default")
      (node (ref "U27") (pin "5") (pinfunction "5_5") (pintype "passive"))
    )
    (net (code "176") (name "unconnected-(U28-Pad3)") (class "Default")
      (node (ref "U28") (pin "3") (pinfunction "3_3") (pintype "passive"))
    )
    (net (code "177") (name "unconnected-(U28-Pad5)") (class "Default")
      (node (ref "U28") (pin "5") (pinfunction "5_5") (pintype "passive"))
    )
    (net (code "178") (name "unconnected-(U29-Pad3)") (class "Default")
      (node (ref "U29") (pin "3") (pinfunction "3_3") (pintype "passive"))
    )
    (net (code "179") (name "unconnected-(U29-Pad5)") (class "Default")
      (node (ref "U29") (pin "5") (pinfunction "5_5") (pintype "passive"))
    )
    (net (code "180") (name "unconnected-(U30-Pad3)") (class "Default")
      (node (ref "U30") (pin "3") (pinfunction "3_3") (pintype "passive"))
    )
    (net (code "181") (name "unconnected-(U30-Pad5)") (class "Default")
      (node (ref "U30") (pin "5") (pinfunction "5_5") (pintype "passive"))
    )
  )
)
